# 1500015_ICLED_Featherwing_HW-V0-3.net
KiCad netlist of a schematic drawn in EAGLE
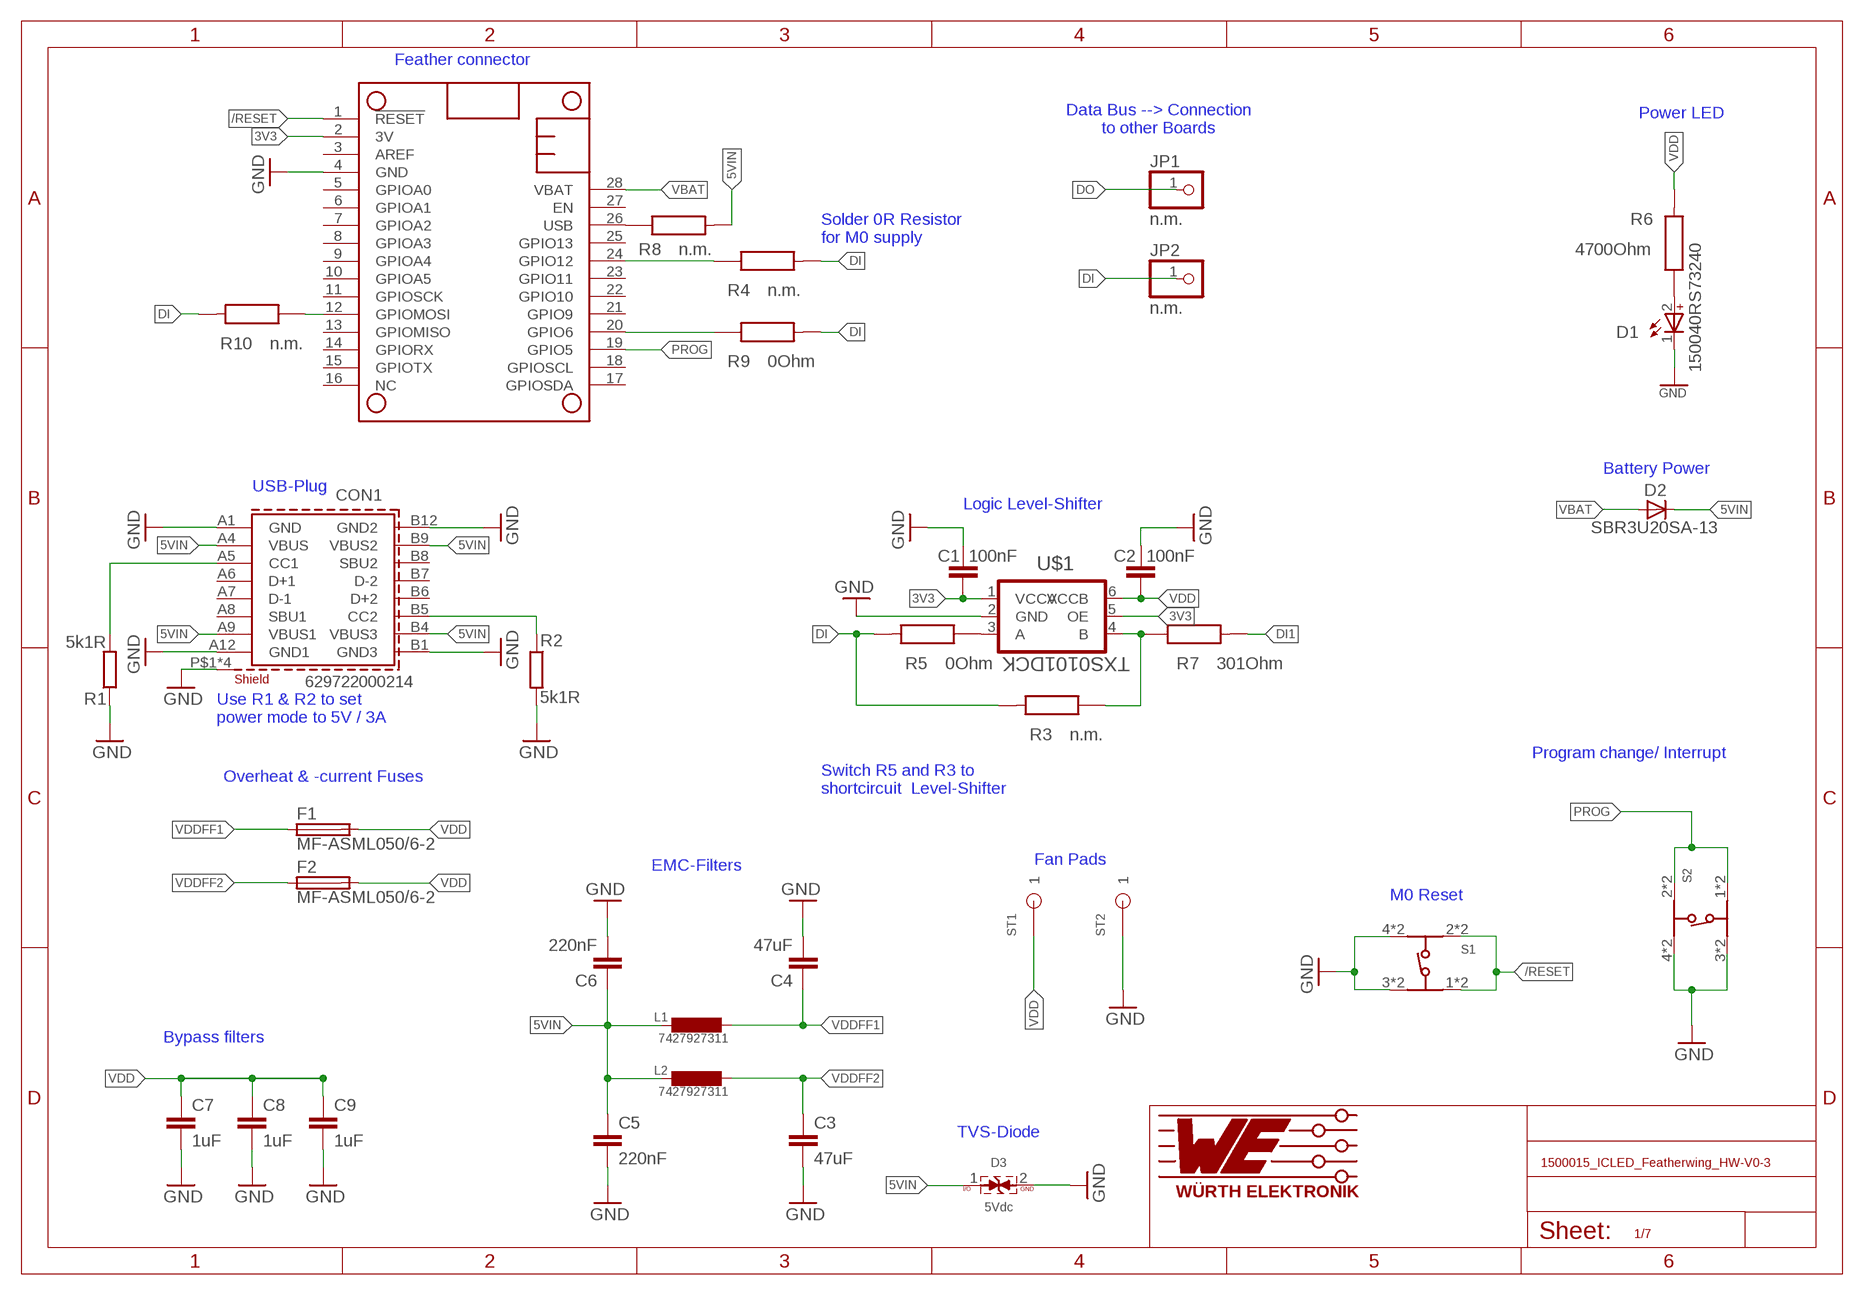
[diagram p0: schematic, sheet 1]
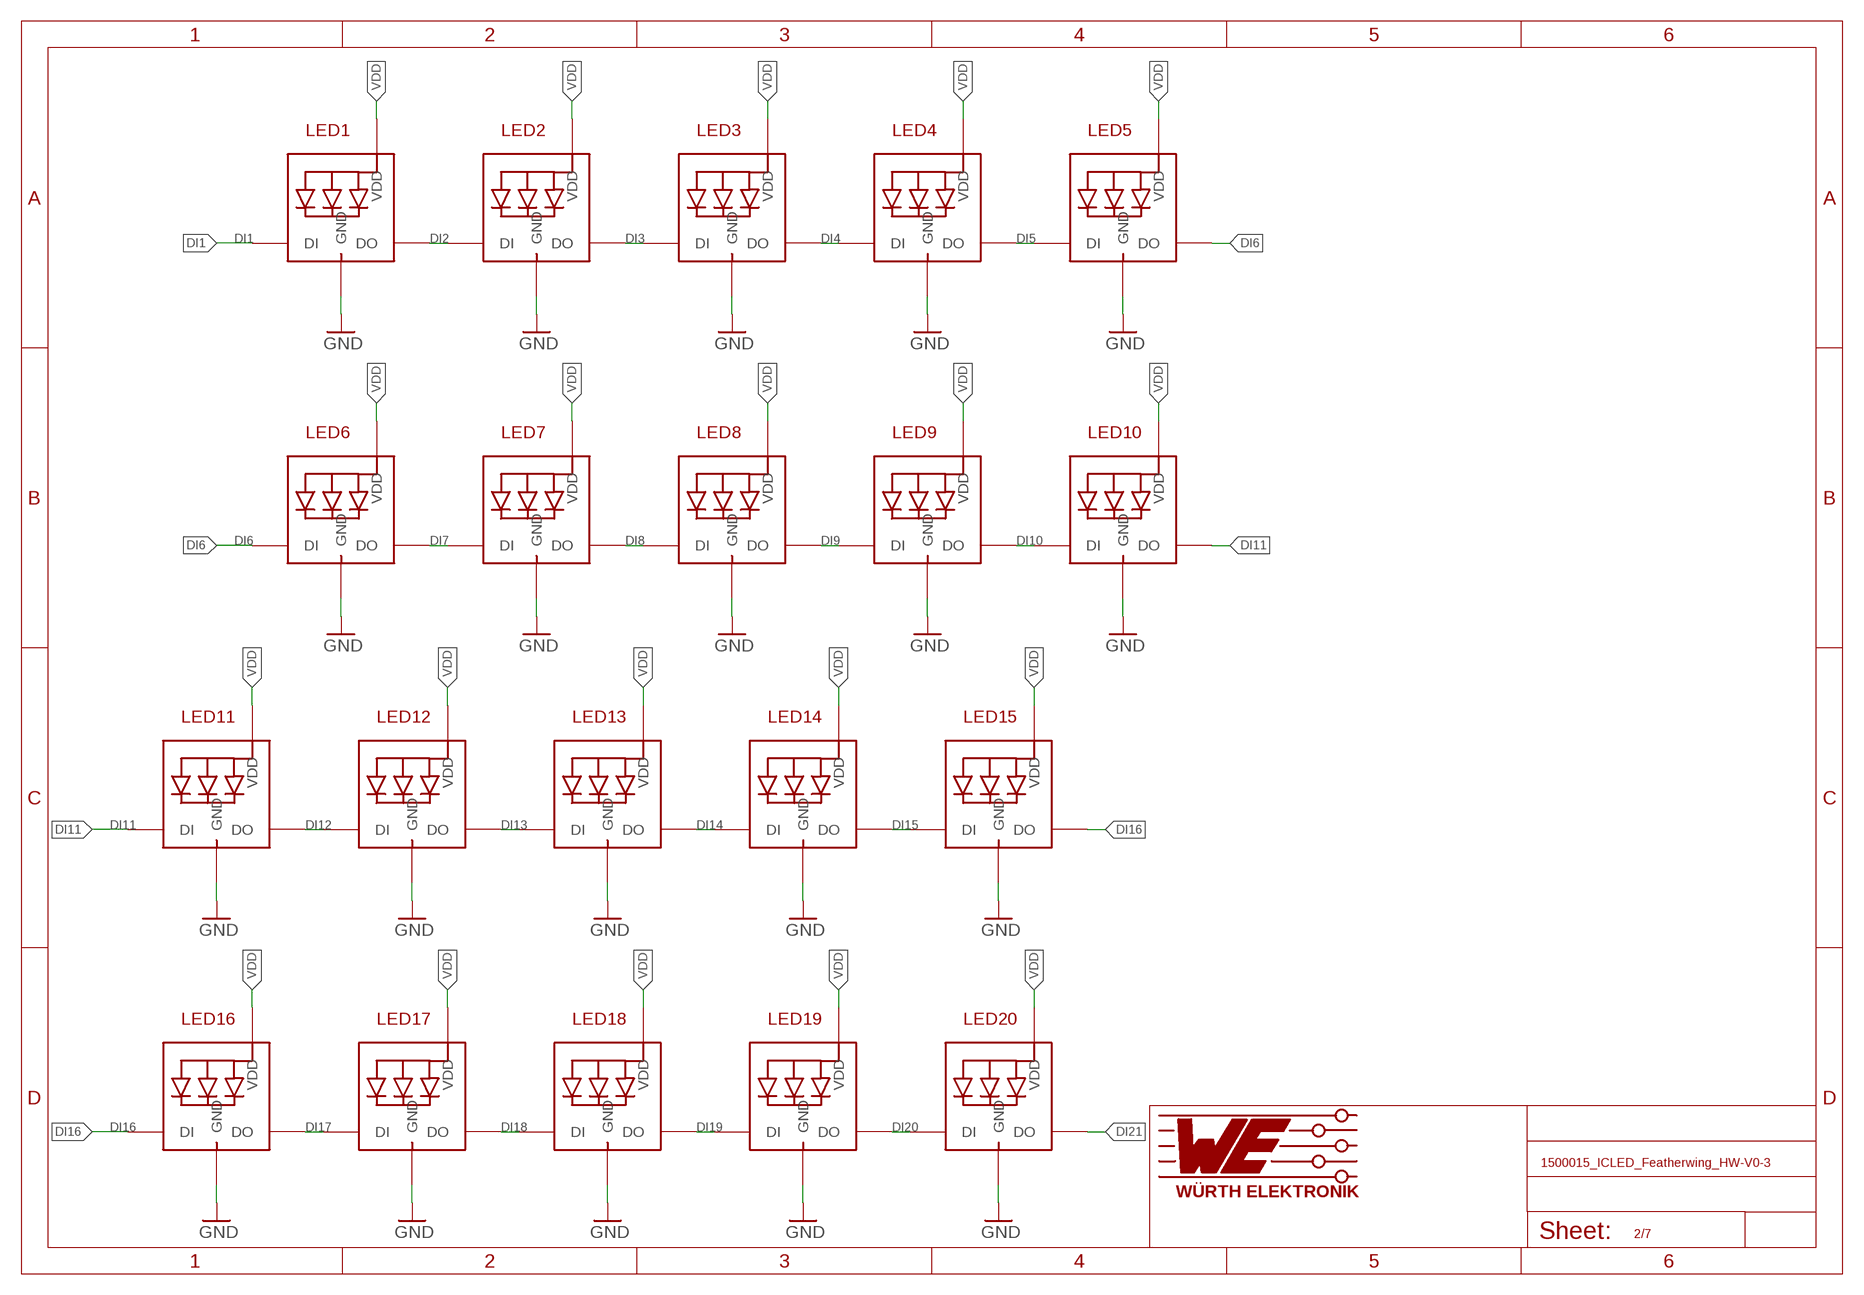
[diagram p1: schematic, sheet 2]
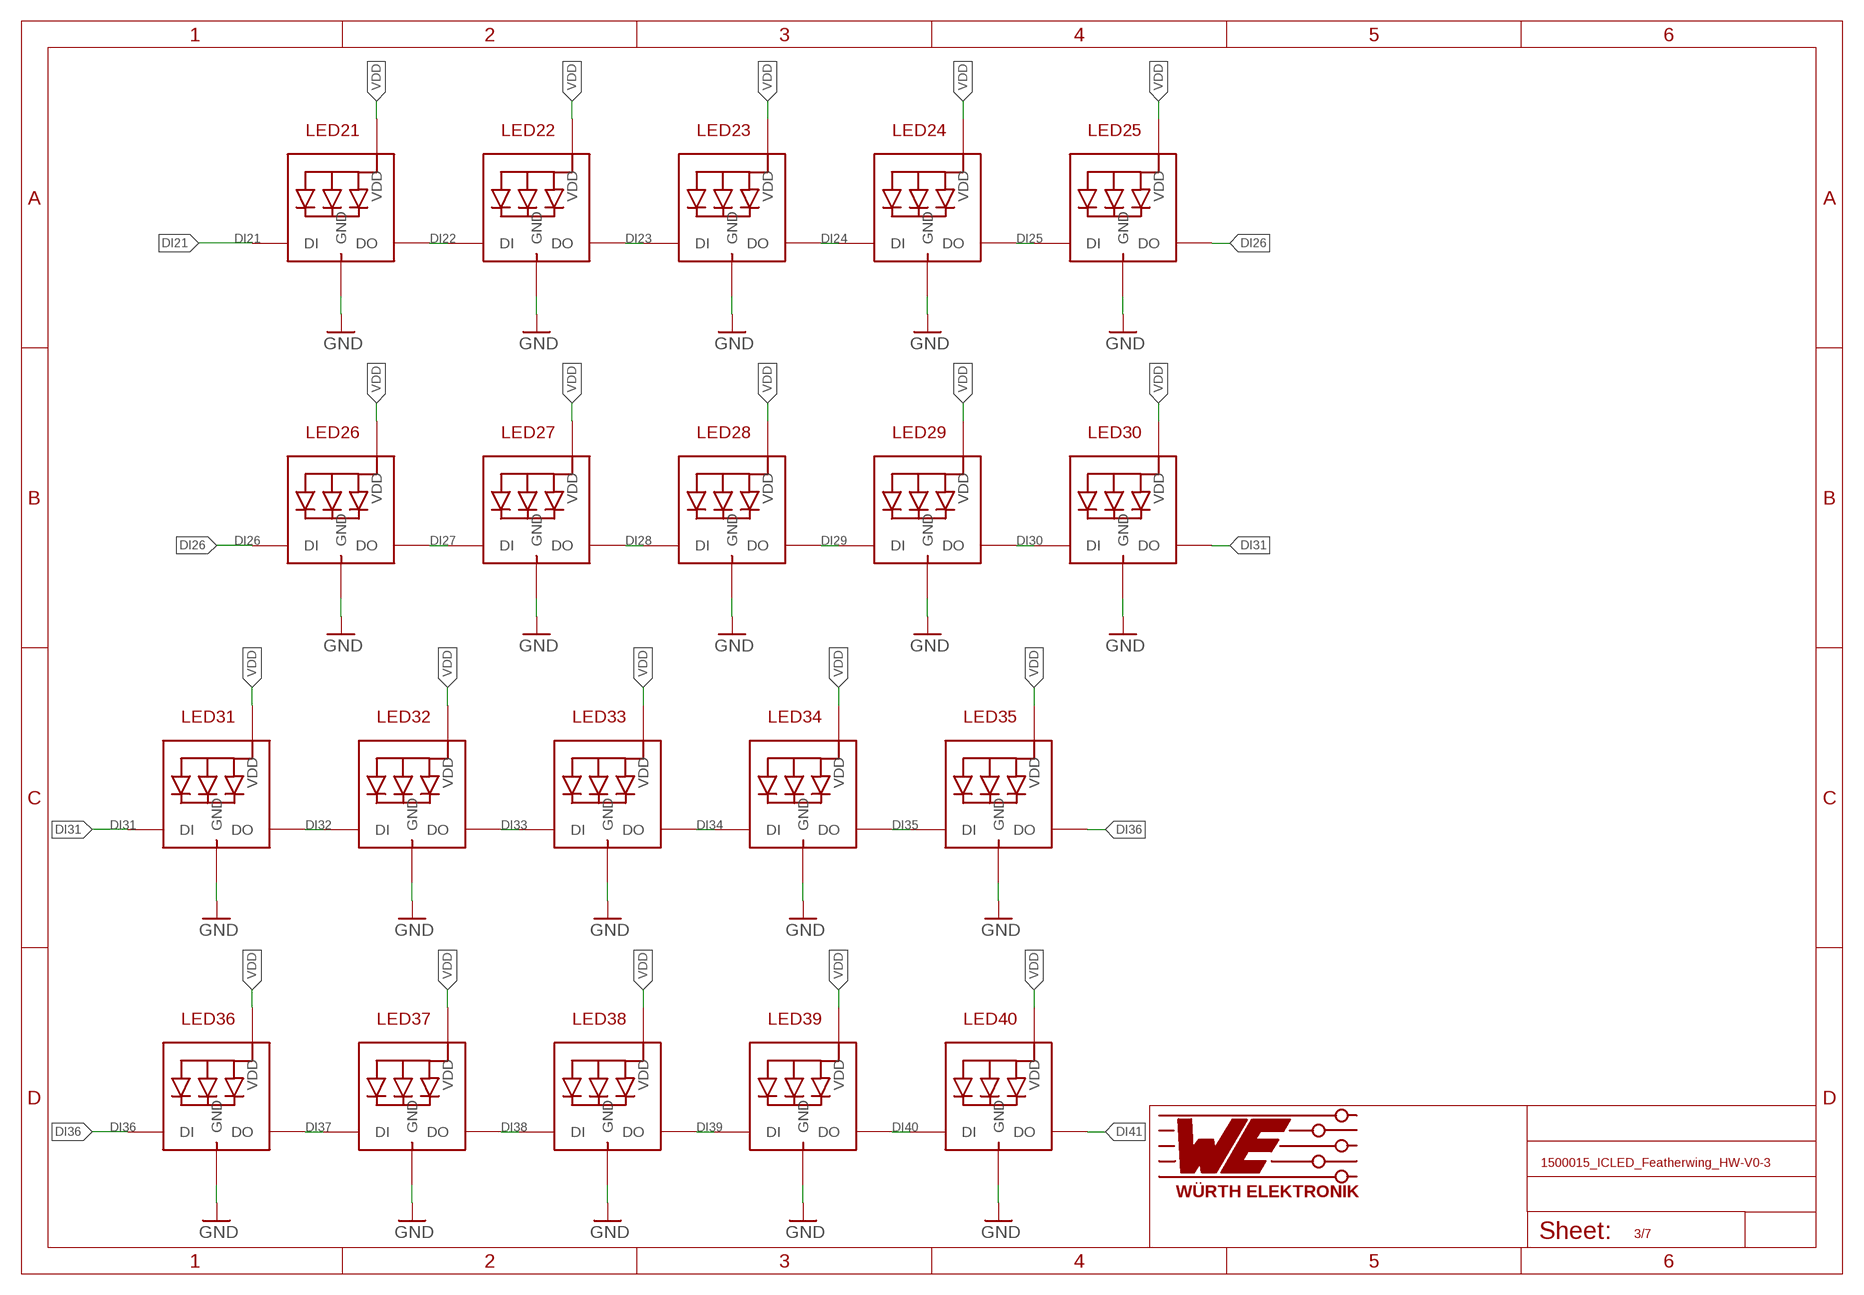
[diagram p2: schematic, sheet 3]
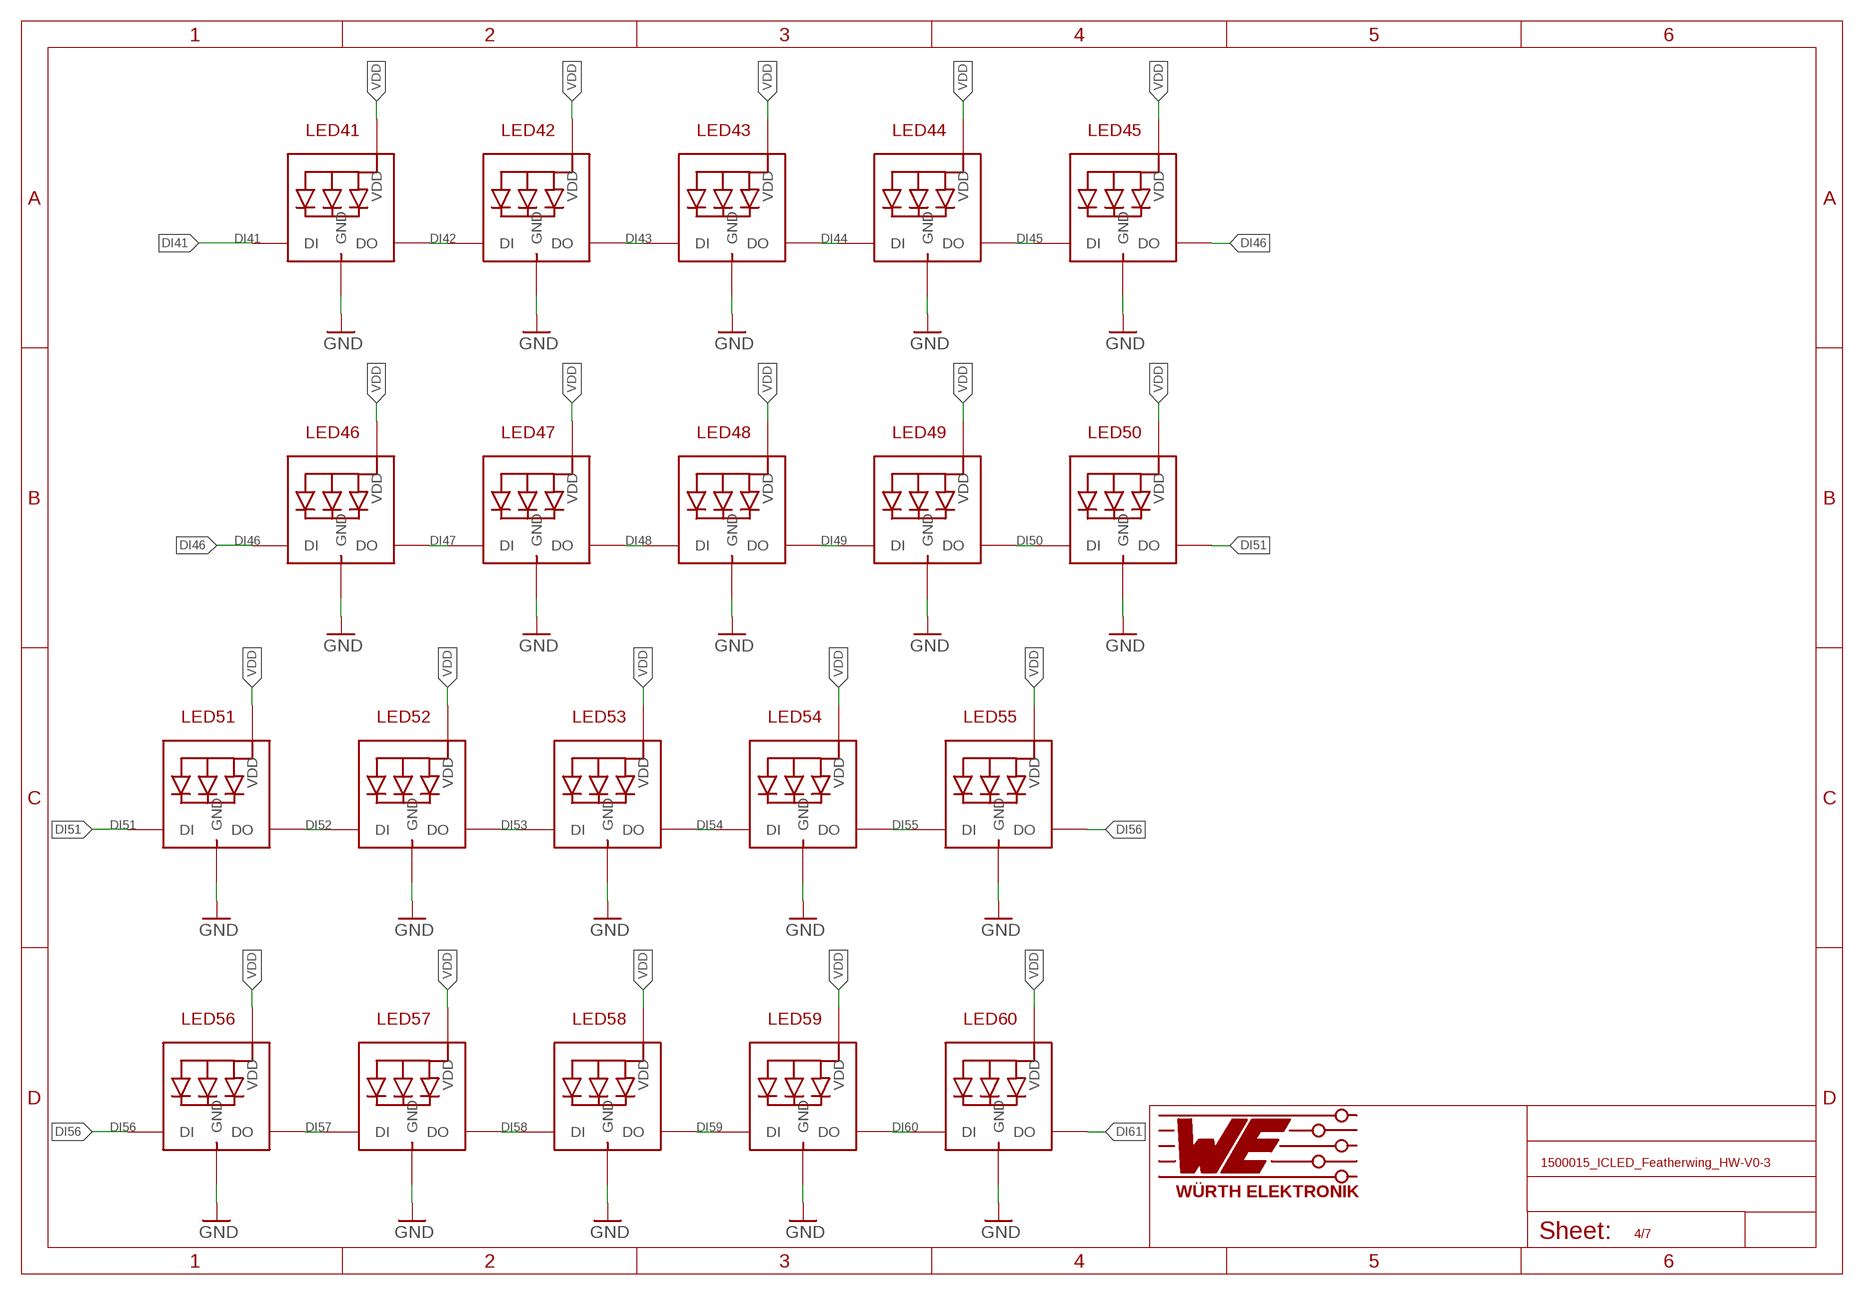
[diagram p3: schematic, sheet 4]
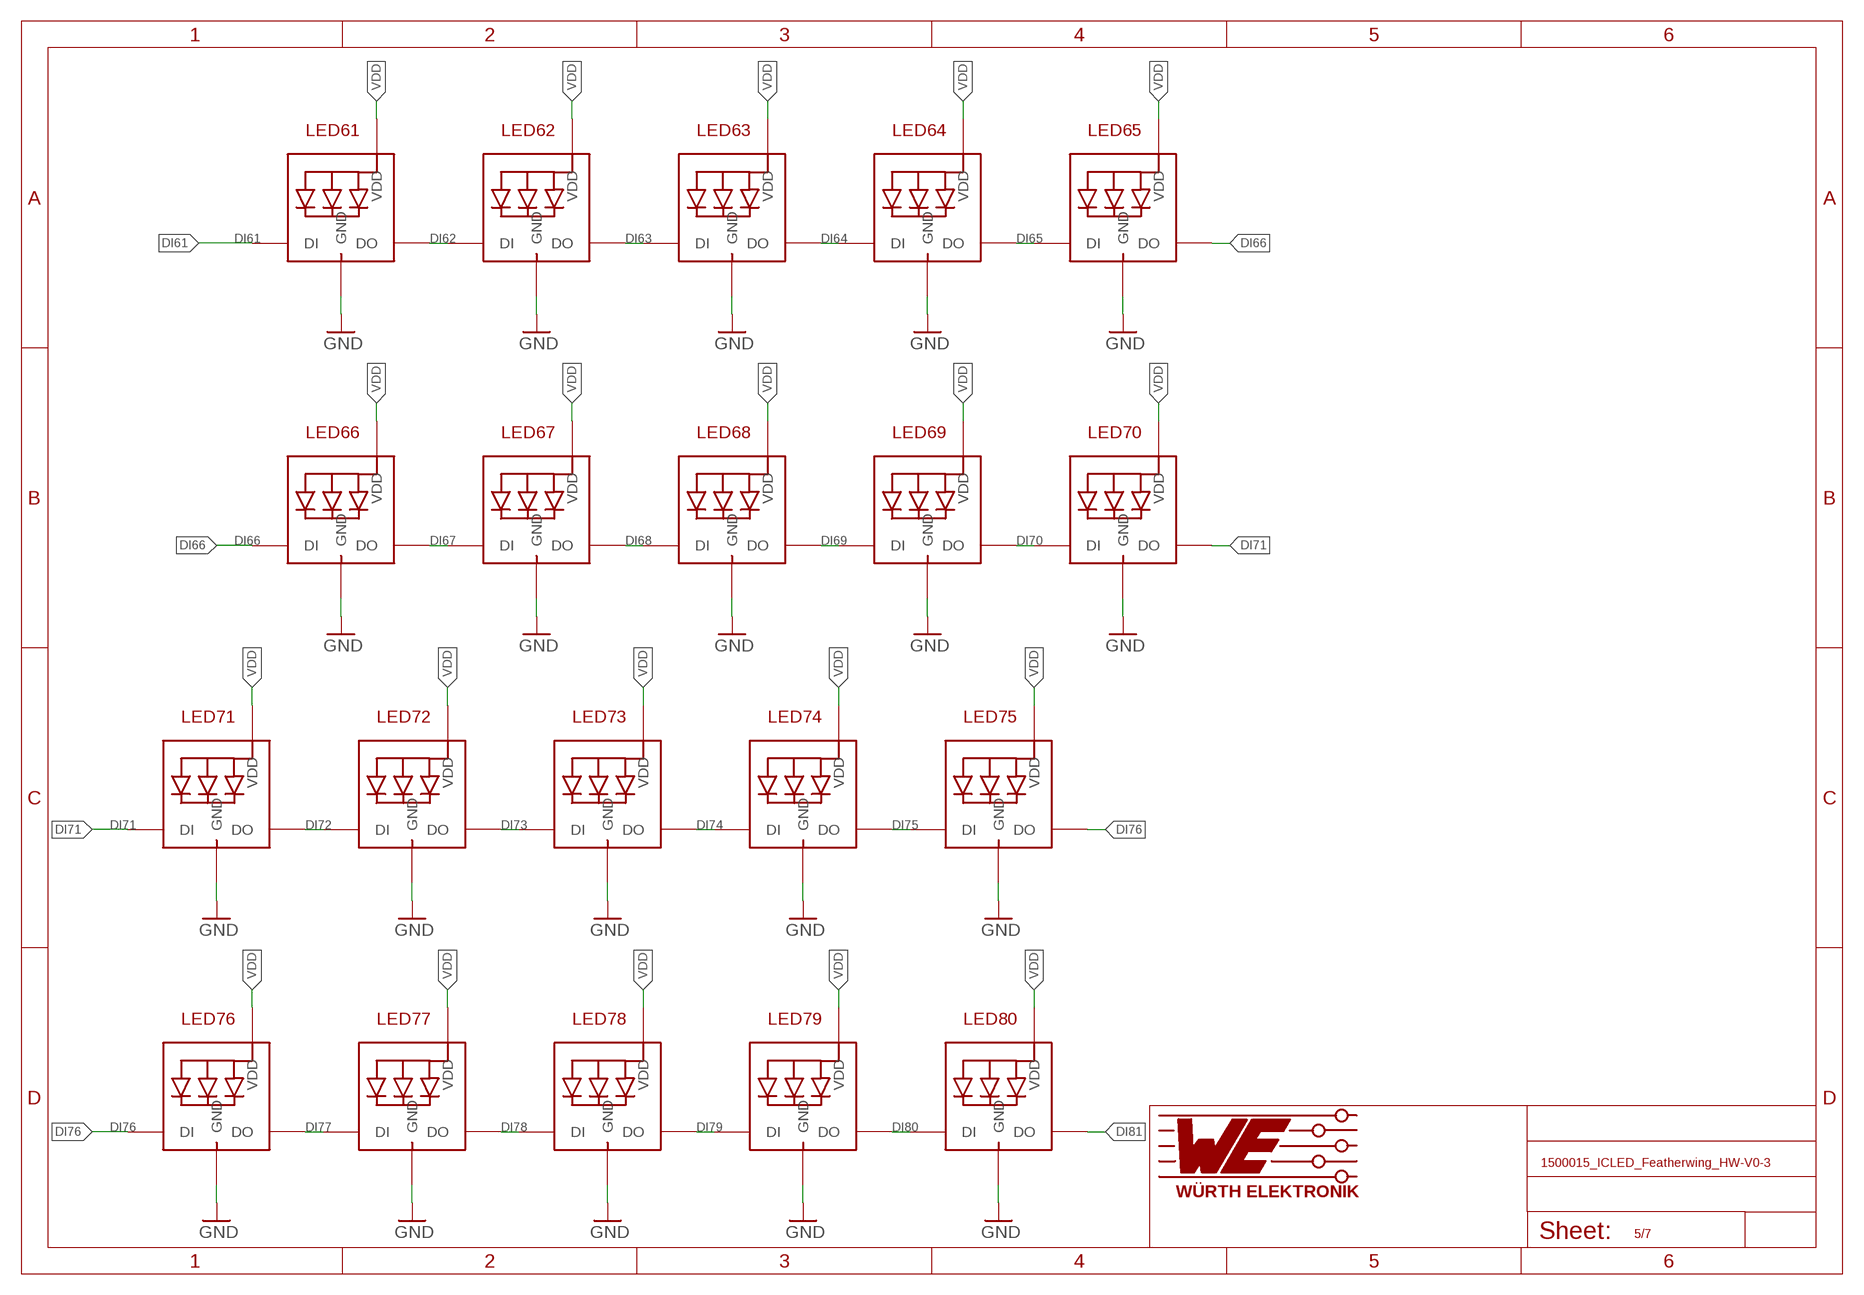
[diagram p4: schematic, sheet 5]
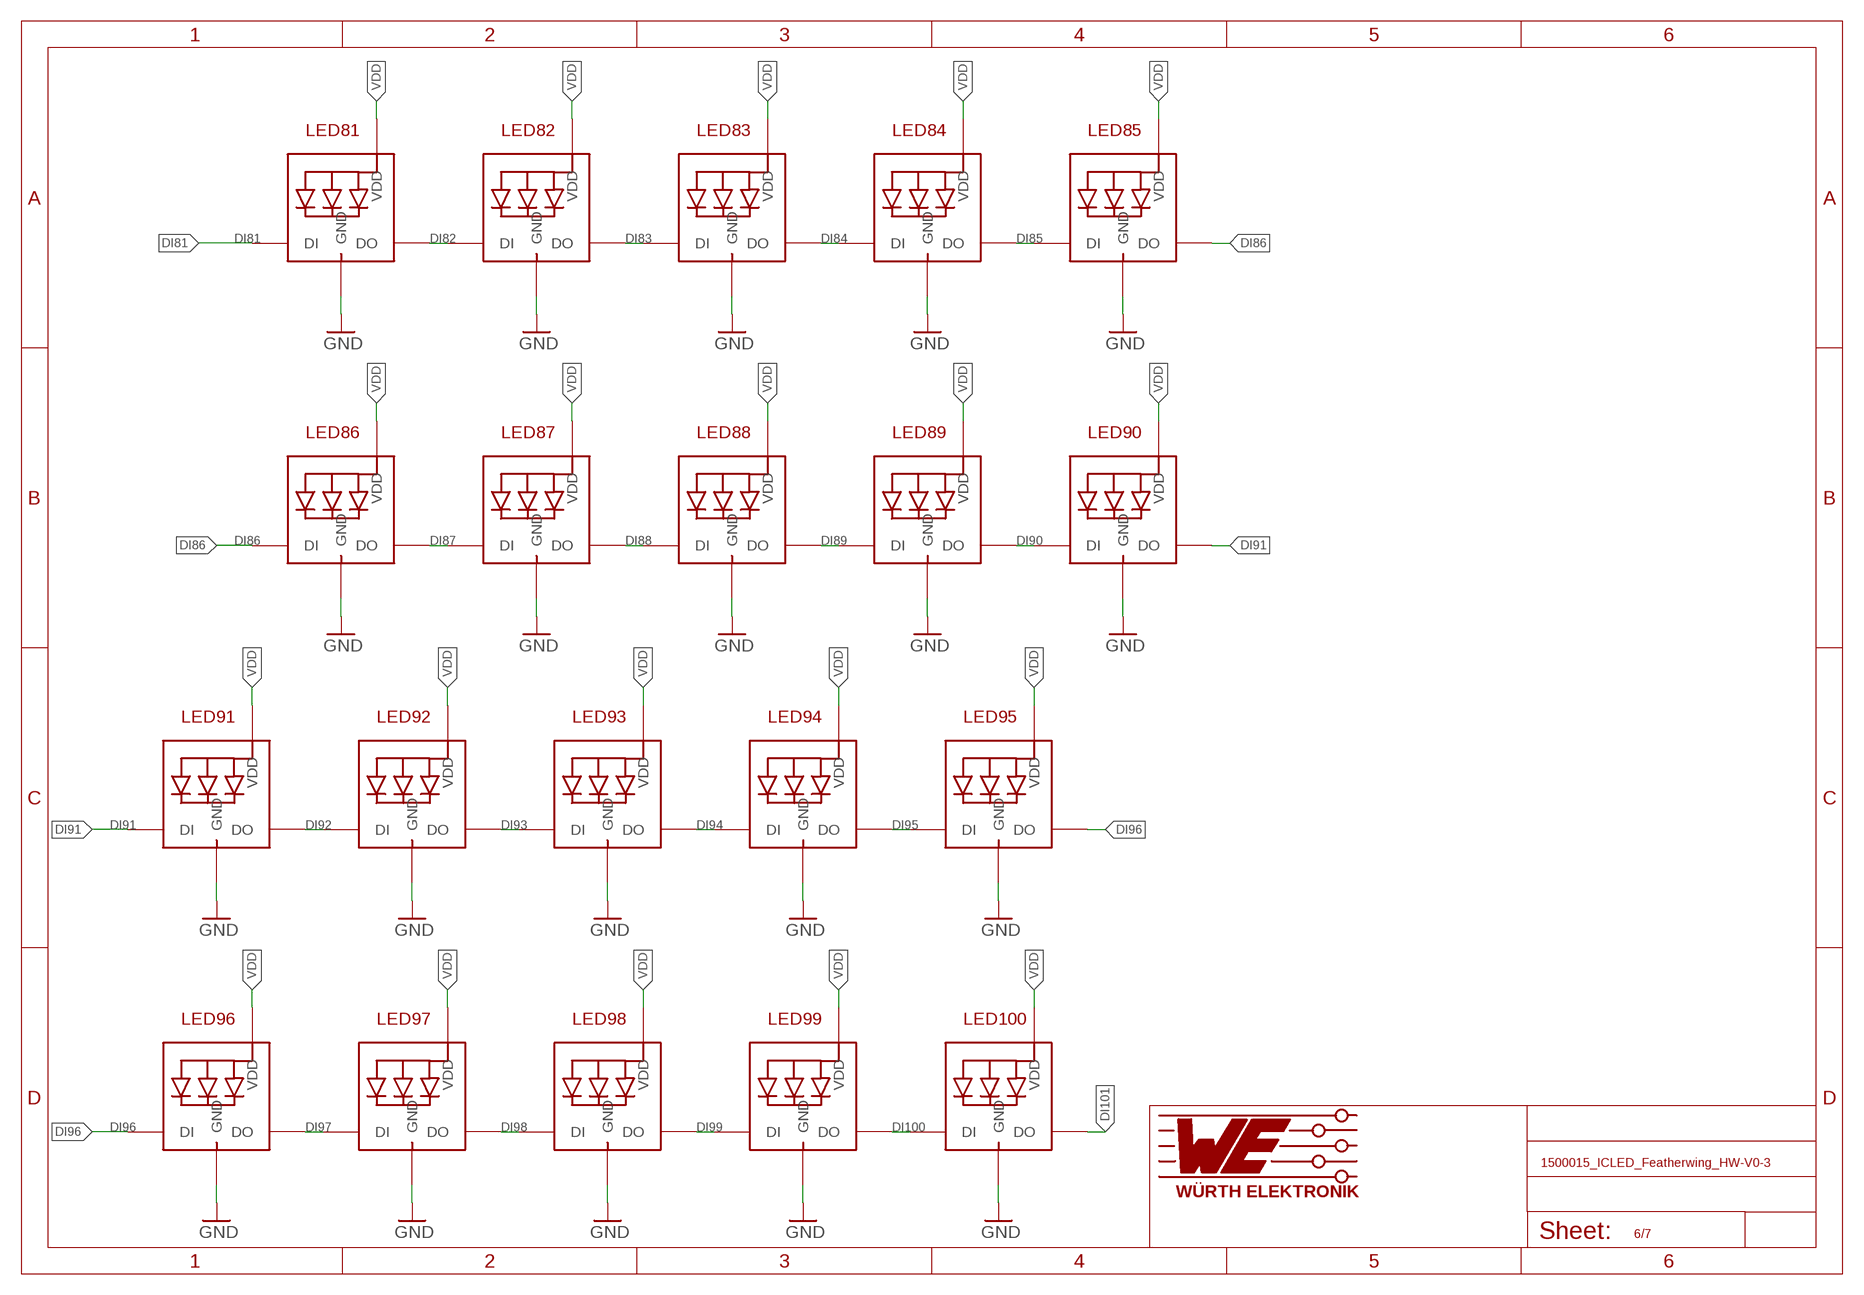
[diagram p5: schematic, sheet 6]
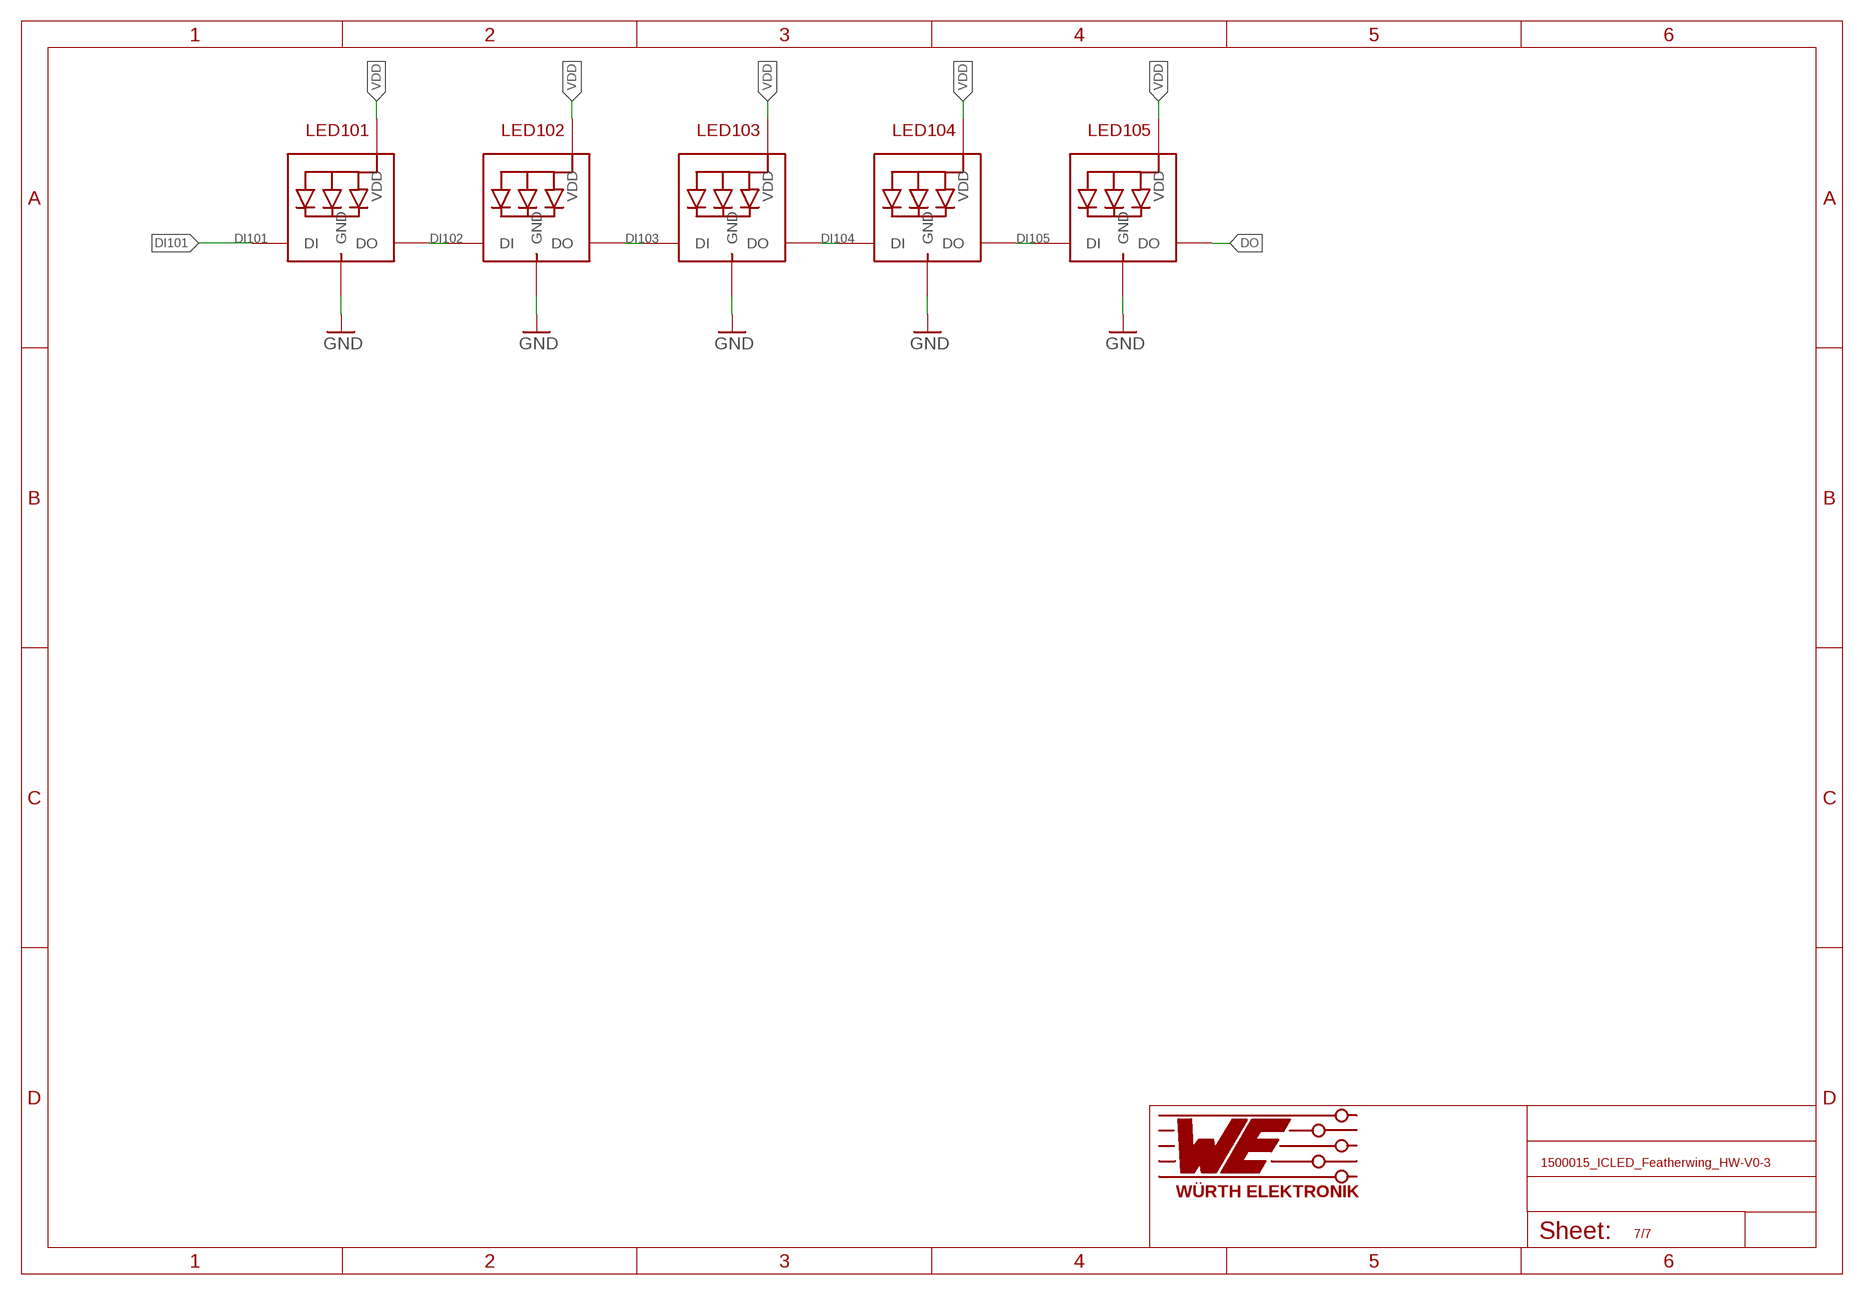
[diagram p6: schematic, sheet 7]

(export (version "E")
  (design (tool "Eeschema 10.0.6"))
  (components
    (comp (ref "LED41")
      (value "1312020030000")
      (footprint "eagle-import:1312020030000_FWANGEPASST")
      (fields (field (name "MANUFACTURER") "Würth Elektronik"))
      (libsource (lib "eagle-import") (part "1312020030000"))
    )
    (comp (ref "LED42")
      (value "1312020030000")
      (footprint "eagle-import:1312020030000_FWANGEPASST")
      (fields (field (name "MANUFACTURER") "Würth Elektronik"))
      (libsource (lib "eagle-import") (part "1312020030000"))
    )
    (comp (ref "LED43")
      (value "1312020030000")
      (footprint "eagle-import:1312020030000_FWANGEPASST")
      (fields (field (name "MANUFACTURER") "Würth Elektronik"))
      (libsource (lib "eagle-import") (part "1312020030000"))
    )
    (comp (ref "LED44")
      (value "1312020030000")
      (footprint "eagle-import:1312020030000_FWANGEPASST")
      (fields (field (name "MANUFACTURER") "Würth Elektronik"))
      (libsource (lib "eagle-import") (part "1312020030000"))
    )
    (comp (ref "LED45")
      (value "1312020030000")
      (footprint "eagle-import:1312020030000_FWANGEPASST")
      (fields (field (name "MANUFACTURER") "Würth Elektronik"))
      (libsource (lib "eagle-import") (part "1312020030000"))
    )
    (comp (ref "LED46")
      (value "1312020030000")
      (footprint "eagle-import:1312020030000_FWANGEPASST")
      (fields (field (name "MANUFACTURER") "Würth Elektronik"))
      (libsource (lib "eagle-import") (part "1312020030000"))
    )
    (comp (ref "LED47")
      (value "1312020030000")
      (footprint "eagle-import:1312020030000_FWANGEPASST")
      (fields (field (name "MANUFACTURER") "Würth Elektronik"))
      (libsource (lib "eagle-import") (part "1312020030000"))
    )
    (comp (ref "LED48")
      (value "1312020030000")
      (footprint "eagle-import:1312020030000_FWANGEPASST")
      (fields (field (name "MANUFACTURER") "Würth Elektronik"))
      (libsource (lib "eagle-import") (part "1312020030000"))
    )
    (comp (ref "LED49")
      (value "1312020030000")
      (footprint "eagle-import:1312020030000_FWANGEPASST")
      (fields (field (name "MANUFACTURER") "Würth Elektronik"))
      (libsource (lib "eagle-import") (part "1312020030000"))
    )
    (comp (ref "LED50")
      (value "1312020030000")
      (footprint "eagle-import:1312020030000_FWANGEPASST")
      (fields (field (name "MANUFACTURER") "Würth Elektronik"))
      (libsource (lib "eagle-import") (part "1312020030000"))
    )
    (comp (ref "LED51")
      (value "1312020030000")
      (footprint "eagle-import:1312020030000_FWANGEPASST")
      (fields (field (name "MANUFACTURER") "Würth Elektronik"))
      (libsource (lib "eagle-import") (part "1312020030000"))
    )
    (comp (ref "LED52")
      (value "1312020030000")
      (footprint "eagle-import:1312020030000_FWANGEPASST")
      (fields (field (name "MANUFACTURER") "Würth Elektronik"))
      (libsource (lib "eagle-import") (part "1312020030000"))
    )
    (comp (ref "LED53")
      (value "1312020030000")
      (footprint "eagle-import:1312020030000_FWANGEPASST")
      (fields (field (name "MANUFACTURER") "Würth Elektronik"))
      (libsource (lib "eagle-import") (part "1312020030000"))
    )
    (comp (ref "LED54")
      (value "1312020030000")
      (footprint "eagle-import:1312020030000_FWANGEPASST")
      (fields (field (name "MANUFACTURER") "Würth Elektronik"))
      (libsource (lib "eagle-import") (part "1312020030000"))
    )
    (comp (ref "LED55")
      (value "1312020030000")
      (footprint "eagle-import:1312020030000_FWANGEPASST")
      (fields (field (name "MANUFACTURER") "Würth Elektronik"))
      (libsource (lib "eagle-import") (part "1312020030000"))
    )
    (comp (ref "LED56")
      (value "1312020030000")
      (footprint "eagle-import:1312020030000_FWANGEPASST")
      (fields (field (name "MANUFACTURER") "Würth Elektronik"))
      (libsource (lib "eagle-import") (part "1312020030000"))
    )
    (comp (ref "LED57")
      (value "1312020030000")
      (footprint "eagle-import:1312020030000_FWANGEPASST")
      (fields (field (name "MANUFACTURER") "Würth Elektronik"))
      (libsource (lib "eagle-import") (part "1312020030000"))
    )
    (comp (ref "LED58")
      (value "1312020030000")
      (footprint "eagle-import:1312020030000_FWANGEPASST")
      (fields (field (name "MANUFACTURER") "Würth Elektronik"))
      (libsource (lib "eagle-import") (part "1312020030000"))
    )
    (comp (ref "LED59")
      (value "1312020030000")
      (footprint "eagle-import:1312020030000_FWANGEPASST")
      (fields (field (name "MANUFACTURER") "Würth Elektronik"))
      (libsource (lib "eagle-import") (part "1312020030000"))
    )
    (comp (ref "LED60")
      (value "1312020030000")
      (footprint "eagle-import:1312020030000_FWANGEPASST")
      (fields (field (name "MANUFACTURER") "Würth Elektronik"))
      (libsource (lib "eagle-import") (part "1312020030000"))
    )
    (comp (ref "LED61")
      (value "1312020030000")
      (footprint "eagle-import:1312020030000_FWANGEPASST")
      (fields (field (name "MANUFACTURER") "Würth Elektronik"))
      (libsource (lib "eagle-import") (part "1312020030000"))
    )
    (comp (ref "LED62")
      (value "1312020030000")
      (footprint "eagle-import:1312020030000_FWANGEPASST")
      (fields (field (name "MANUFACTURER") "Würth Elektronik"))
      (libsource (lib "eagle-import") (part "1312020030000"))
    )
    (comp (ref "LED63")
      (value "1312020030000")
      (footprint "eagle-import:1312020030000_FWANGEPASST")
      (fields (field (name "MANUFACTURER") "Würth Elektronik"))
      (libsource (lib "eagle-import") (part "1312020030000"))
    )
    (comp (ref "LED64")
      (value "1312020030000")
      (footprint "eagle-import:1312020030000_FWANGEPASST")
      (fields (field (name "MANUFACTURER") "Würth Elektronik"))
      (libsource (lib "eagle-import") (part "1312020030000"))
    )
    (comp (ref "LED65")
      (value "1312020030000")
      (footprint "eagle-import:1312020030000_FWANGEPASST")
      (fields (field (name "MANUFACTURER") "Würth Elektronik"))
      (libsource (lib "eagle-import") (part "1312020030000"))
    )
    (comp (ref "LED66")
      (value "1312020030000")
      (footprint "eagle-import:1312020030000_FWANGEPASST")
      (fields (field (name "MANUFACTURER") "Würth Elektronik"))
      (libsource (lib "eagle-import") (part "1312020030000"))
    )
    (comp (ref "LED67")
      (value "1312020030000")
      (footprint "eagle-import:1312020030000_FWANGEPASST")
      (fields (field (name "MANUFACTURER") "Würth Elektronik"))
      (libsource (lib "eagle-import") (part "1312020030000"))
    )
    (comp (ref "LED68")
      (value "1312020030000")
      (footprint "eagle-import:1312020030000_FWANGEPASST")
      (fields (field (name "MANUFACTURER") "Würth Elektronik"))
      (libsource (lib "eagle-import") (part "1312020030000"))
    )
    (comp (ref "LED69")
      (value "1312020030000")
      (footprint "eagle-import:1312020030000_FWANGEPASST")
      (fields (field (name "MANUFACTURER") "Würth Elektronik"))
      (libsource (lib "eagle-import") (part "1312020030000"))
    )
    (comp (ref "LED70")
      (value "1312020030000")
      (footprint "eagle-import:1312020030000_FWANGEPASST")
      (fields (field (name "MANUFACTURER") "Würth Elektronik"))
      (libsource (lib "eagle-import") (part "1312020030000"))
    )
    (comp (ref "LED71")
      (value "1312020030000")
      (footprint "eagle-import:1312020030000_FWANGEPASST")
      (fields (field (name "MANUFACTURER") "Würth Elektronik"))
      (libsource (lib "eagle-import") (part "1312020030000"))
    )
    (comp (ref "LED72")
      (value "1312020030000")
      (footprint "eagle-import:1312020030000_FWANGEPASST")
      (fields (field (name "MANUFACTURER") "Würth Elektronik"))
      (libsource (lib "eagle-import") (part "1312020030000"))
    )
    (comp (ref "LED73")
      (value "1312020030000")
      (footprint "eagle-import:1312020030000_FWANGEPASST")
      (fields (field (name "MANUFACTURER") "Würth Elektronik"))
      (libsource (lib "eagle-import") (part "1312020030000"))
    )
    (comp (ref "LED74")
      (value "1312020030000")
      (footprint "eagle-import:1312020030000_FWANGEPASST")
      (fields (field (name "MANUFACTURER") "Würth Elektronik"))
      (libsource (lib "eagle-import") (part "1312020030000"))
    )
    (comp (ref "LED75")
      (value "1312020030000")
      (footprint "eagle-import:1312020030000_FWANGEPASST")
      (fields (field (name "MANUFACTURER") "Würth Elektronik"))
      (libsource (lib "eagle-import") (part "1312020030000"))
    )
    (comp (ref "LED76")
      (value "1312020030000")
      (footprint "eagle-import:1312020030000_FWANGEPASST")
      (fields (field (name "MANUFACTURER") "Würth Elektronik"))
      (libsource (lib "eagle-import") (part "1312020030000"))
    )
    (comp (ref "LED77")
      (value "1312020030000")
      (footprint "eagle-import:1312020030000_FWANGEPASST")
      (fields (field (name "MANUFACTURER") "Würth Elektronik"))
      (libsource (lib "eagle-import") (part "1312020030000"))
    )
    (comp (ref "LED78")
      (value "1312020030000")
      (footprint "eagle-import:1312020030000_FWANGEPASST")
      (fields (field (name "MANUFACTURER") "Würth Elektronik"))
      (libsource (lib "eagle-import") (part "1312020030000"))
    )
    (comp (ref "LED79")
      (value "1312020030000")
      (footprint "eagle-import:1312020030000_FWANGEPASST")
      (fields (field (name "MANUFACTURER") "Würth Elektronik"))
      (libsource (lib "eagle-import") (part "1312020030000"))
    )
    (comp (ref "LED80")
      (value "1312020030000")
      (footprint "eagle-import:1312020030000_FWANGEPASST")
      (fields (field (name "MANUFACTURER") "Würth Elektronik"))
      (libsource (lib "eagle-import") (part "1312020030000"))
    )
    (comp (ref "LED1")
      (value "1312020030000")
      (footprint "eagle-import:1312020030000_FWANGEPASST")
      (fields (field (name "MANUFACTURER") "Würth Elektronik"))
      (libsource (lib "eagle-import") (part "1312020030000"))
    )
    (comp (ref "LED2")
      (value "1312020030000")
      (footprint "eagle-import:1312020030000_FWANGEPASST")
      (fields (field (name "MANUFACTURER") "Würth Elektronik"))
      (libsource (lib "eagle-import") (part "1312020030000"))
    )
    (comp (ref "LED3")
      (value "1312020030000")
      (footprint "eagle-import:1312020030000_FWANGEPASST")
      (fields (field (name "MANUFACTURER") "Würth Elektronik"))
      (libsource (lib "eagle-import") (part "1312020030000"))
    )
    (comp (ref "LED4")
      (value "1312020030000")
      (footprint "eagle-import:1312020030000_FWANGEPASST")
      (fields (field (name "MANUFACTURER") "Würth Elektronik"))
      (libsource (lib "eagle-import") (part "1312020030000"))
    )
    (comp (ref "LED5")
      (value "1312020030000")
      (footprint "eagle-import:1312020030000_FWANGEPASST")
      (fields (field (name "MANUFACTURER") "Würth Elektronik"))
      (libsource (lib "eagle-import") (part "1312020030000"))
    )
    (comp (ref "LED6")
      (value "1312020030000")
      (footprint "eagle-import:1312020030000_FWANGEPASST")
      (fields (field (name "MANUFACTURER") "Würth Elektronik"))
      (libsource (lib "eagle-import") (part "1312020030000"))
    )
    (comp (ref "LED7")
      (value "1312020030000")
      (footprint "eagle-import:1312020030000_FWANGEPASST")
      (fields (field (name "MANUFACTURER") "Würth Elektronik"))
      (libsource (lib "eagle-import") (part "1312020030000"))
    )
    (comp (ref "LED8")
      (value "1312020030000")
      (footprint "eagle-import:1312020030000_FWANGEPASST")
      (fields (field (name "MANUFACTURER") "Würth Elektronik"))
      (libsource (lib "eagle-import") (part "1312020030000"))
    )
    (comp (ref "LED9")
      (value "1312020030000")
      (footprint "eagle-import:1312020030000_FWANGEPASST")
      (fields (field (name "MANUFACTURER") "Würth Elektronik"))
      (libsource (lib "eagle-import") (part "1312020030000"))
    )
    (comp (ref "LED10")
      (value "1312020030000")
      (footprint "eagle-import:1312020030000_FWANGEPASST")
      (fields (field (name "MANUFACTURER") "Würth Elektronik"))
      (libsource (lib "eagle-import") (part "1312020030000"))
    )
    (comp (ref "LED11")
      (value "1312020030000")
      (footprint "eagle-import:1312020030000_FWANGEPASST")
      (fields (field (name "MANUFACTURER") "Würth Elektronik"))
      (libsource (lib "eagle-import") (part "1312020030000"))
    )
    (comp (ref "LED12")
      (value "1312020030000")
      (footprint "eagle-import:1312020030000_FWANGEPASST")
      (fields (field (name "MANUFACTURER") "Würth Elektronik"))
      (libsource (lib "eagle-import") (part "1312020030000"))
    )
    (comp (ref "LED13")
      (value "1312020030000")
      (footprint "eagle-import:1312020030000_FWANGEPASST")
      (fields (field (name "MANUFACTURER") "Würth Elektronik"))
      (libsource (lib "eagle-import") (part "1312020030000"))
    )
    (comp (ref "LED14")
      (value "1312020030000")
      (footprint "eagle-import:1312020030000_FWANGEPASST")
      (fields (field (name "MANUFACTURER") "Würth Elektronik"))
      (libsource (lib "eagle-import") (part "1312020030000"))
    )
    (comp (ref "LED15")
      (value "1312020030000")
      (footprint "eagle-import:1312020030000_FWANGEPASST")
      (fields (field (name "MANUFACTURER") "Würth Elektronik"))
      (libsource (lib "eagle-import") (part "1312020030000"))
    )
    (comp (ref "LED16")
      (value "1312020030000")
      (footprint "eagle-import:1312020030000_FWANGEPASST")
      (fields (field (name "MANUFACTURER") "Würth Elektronik"))
      (libsource (lib "eagle-import") (part "1312020030000"))
    )
    (comp (ref "LED17")
      (value "1312020030000")
      (footprint "eagle-import:1312020030000_FWANGEPASST")
      (fields (field (name "MANUFACTURER") "Würth Elektronik"))
      (libsource (lib "eagle-import") (part "1312020030000"))
    )
    (comp (ref "LED18")
      (value "1312020030000")
      (footprint "eagle-import:1312020030000_FWANGEPASST")
      (fields (field (name "MANUFACTURER") "Würth Elektronik"))
      (libsource (lib "eagle-import") (part "1312020030000"))
    )
    (comp (ref "LED19")
      (value "1312020030000")
      (footprint "eagle-import:1312020030000_FWANGEPASST")
      (fields (field (name "MANUFACTURER") "Würth Elektronik"))
      (libsource (lib "eagle-import") (part "1312020030000"))
    )
    (comp (ref "LED20")
      (value "1312020030000")
      (footprint "eagle-import:1312020030000_FWANGEPASST")
      (fields (field (name "MANUFACTURER") "Würth Elektronik"))
      (libsource (lib "eagle-import") (part "1312020030000"))
    )
    (comp (ref "C1")
      (value "100nF")
      (footprint "eagle-import:C0402_IPC")
      (fields (field (name "MANUFACTURER") "Würth Elektronik"))
      (libsource (lib "eagle-import") (part "C0402_IPC100NF"))
    )
    (comp (ref "C2")
      (value "100nF")
      (footprint "eagle-import:C0402_IPC")
      (fields (field (name "MANUFACTURER") "Würth Elektronik"))
      (libsource (lib "eagle-import") (part "C0402_IPC100NF"))
    )
    (comp (ref "C3")
      (value "47uF")
      (footprint "eagle-import:C0805")
      (fields
        (field (name "MANUFACTURER") "Würth Elektronik")
        (field (name "NR") "885012107006")
        (field (name "SPG") "6.3V")
      )
      (libsource (lib "eagle-import") (part "C0805"))
    )
    (comp (ref "C4")
      (value "47uF")
      (footprint "eagle-import:C0805")
      (fields
        (field (name "MANUFACTURER") "Würth Elektronik")
        (field (name "NR") "885012107006")
        (field (name "SPG") "6.3V")
      )
      (libsource (lib "eagle-import") (part "C0805"))
    )
    (comp (ref "C5")
      (value "220nF")
      (footprint "eagle-import:C0603_IPC")
      (fields
        (field (name "MANUFACTURER") "Wurth Elektronik")
        (field (name "NR") "885012206125")
        (field (name "SPG") "50V")
        (field (name "TOL") "5%")
      )
      (libsource (lib "eagle-import") (part "C0603_IPC220N"))
    )
    (comp (ref "C6")
      (value "220nF")
      (footprint "eagle-import:C0603_IPC")
      (fields
        (field (name "MANUFACTURER") "Wurth Elektronik")
        (field (name "NR") "885012206125")
        (field (name "SPG") "50V")
        (field (name "TOL") "5%")
      )
      (libsource (lib "eagle-import") (part "C0603_IPC220N"))
    )
    (comp (ref "C7")
      (value "1uF")
      (footprint "eagle-import:C0402_IPC")
      (fields (field (name "MANUFACTURER") "Würth Elektronik"))
      (libsource (lib "eagle-import") (part "C0402_IPC1UF"))
    )
    (comp (ref "C8")
      (value "1uF")
      (footprint "eagle-import:C0402_IPC")
      (fields (field (name "MANUFACTURER") "Würth Elektronik"))
      (libsource (lib "eagle-import") (part "C0402_IPC1UF"))
    )
    (comp (ref "C9")
      (value "1uF")
      (footprint "eagle-import:C0402_IPC")
      (fields (field (name "MANUFACTURER") "Würth Elektronik"))
      (libsource (lib "eagle-import") (part "C0402_IPC1UF"))
    )
    (comp (ref "CON1")
      (value "629722000214")
      (footprint "eagle-import:629722000214")
      (libsource (lib "eagle-import") (part "629722000214"))
    )
    (comp (ref "D1")
      (value "150040RS73240")
      (footprint "eagle-import:WL-SMCC_0402")
      (libsource (lib "eagle-import") (part "WL-SMCC_0402_150040RS73240"))
    )
    (comp (ref "D2")
      (value "SBR3U20SA-13")
      (footprint "eagle-import:SBR3U20SA")
      (fields (field (name "MANUFACTURER") "Diodes Inc"))
      (libsource (lib "eagle-import") (part "SBR3U20SA-13"))
    )
    (comp (ref "D3")
      (value "5Vdc")
      (footprint "eagle-import:WE-TVS_DFN1610-2L")
      (libsource (lib "eagle-import") (part "WE-TVS_DFN1610-2L_824032815"))
    )
    (comp (ref "F1")
      (value "MF-ASML050/6-2")
      (footprint "eagle-import:0402")
      (fields (field (name "MANUFACTURER") "Bourns"))
      (libsource (lib "eagle-import") (part "ERB-RD2R00X"))
    )
    (comp (ref "F2")
      (value "MF-ASML050/6-2")
      (footprint "eagle-import:0402")
      (fields (field (name "MANUFACTURER") "Bourns"))
      (libsource (lib "eagle-import") (part "ERB-RD2R00X"))
    )
    (comp (ref "JP1")
      (value "n.m.")
      (footprint "eagle-import:1X01_R")
      (libsource (lib "eagle-import") (part "PINHD-1X1/R"))
    )
    (comp (ref "JP2")
      (value "n.m.")
      (footprint "eagle-import:1X01_R")
      (libsource (lib "eagle-import") (part "PINHD-1X1/R"))
    )
    (comp (ref "L1")
      (value "7427927311")
      (footprint "eagle-import:L0402_WE_FERRIT")
      (fields (field (name "MANUFACTURER") "Würth Elektronik "))
      (libsource (lib "eagle-import") (part "LL0402_WE_FERRIT"))
    )
    (comp (ref "L2")
      (value "7427927311")
      (footprint "eagle-import:L0402_WE_FERRIT")
      (fields (field (name "MANUFACTURER") "Würth Elektronik "))
      (libsource (lib "eagle-import") (part "LL0402_WE_FERRIT"))
    )
    (comp (ref "MS1")
      (value "FEATHERWING")
      (footprint "eagle-import:FEATHERWING")
      (libsource (lib "eagle-import") (part "FEATHERWING"))
    )
    (comp (ref "R1")
      (value "5k1R")
      (footprint "eagle-import:R0402_IPC")
      (fields (field (name "NR") " RC0402FR-075K1L"))
      (libsource (lib "eagle-import") (part "R0402_IPC10KR"))
    )
    (comp (ref "R2")
      (value "5k1R")
      (footprint "eagle-import:R0402_IPC")
      (fields (field (name "NR") " RC0402FR-075K1L"))
      (libsource (lib "eagle-import") (part "R0402_IPC10KR"))
    )
    (comp (ref "R3")
      (value "n.m.")
      (footprint "eagle-import:WRIS-RSKS_0603_WAVE")
      (libsource (lib "eagle-import") (part "WRIS-RSKS_0603_WAVE_560112116001"))
    )
    (comp (ref "R4")
      (value "n.m.")
      (footprint "eagle-import:WRIS-RSKS_0402")
      (libsource (lib "eagle-import") (part "WRIS-RSKS_0402_560112110001"))
    )
    (comp (ref "R5")
      (value "0Ohm")
      (footprint "eagle-import:WRIS-RSKS_0603_WAVE")
      (libsource (lib "eagle-import") (part "WRIS-RSKS_0603_WAVE_560112116001"))
    )
    (comp (ref "R6")
      (value "4700Ohm")
      (footprint "eagle-import:WRIS-RSKS_0402")
      (libsource (lib "eagle-import") (part "WRIS-RSKS_0402_560112110245"))
    )
    (comp (ref "R7")
      (value "301Ohm")
      (footprint "eagle-import:WRIS-RSKS_0402")
      (libsource (lib "eagle-import") (part "WRIS-RSKS_0402_560112110092"))
    )
    (comp (ref "R8")
      (value "n.m.")
      (footprint "eagle-import:WRIS-RSKS_0402")
      (libsource (lib "eagle-import") (part "WRIS-RSKS_0402_560112110001"))
    )
    (comp (ref "R9")
      (value "0Ohm")
      (footprint "eagle-import:WRIS-RSKS_0603_WAVE")
      (libsource (lib "eagle-import") (part "WRIS-RSKS_0603_WAVE_560112116001"))
    )
    (comp (ref "R10")
      (value "n.m.")
      (footprint "eagle-import:WRIS-RSKS_0603_WAVE")
      (libsource (lib "eagle-import") (part "WRIS-RSKS_0603_WAVE_560112116001"))
    )
    (comp (ref "S1")
      (value "434331013822")
      (footprint "eagle-import:434331013822_ICLEDFW_ANGEPASST")
      (fields (field (name "MANUFACTURER") "Würth Elektronik"))
      (libsource (lib "eagle-import") (part "434331013822_ANGEPASST"))
    )
    (comp (ref "S2")
      (value "434331013822")
      (footprint "eagle-import:434331013822_ICLEDFW_ANGEPASST")
      (fields (field (name "MANUFACTURER") "Würth Elektronik"))
      (libsource (lib "eagle-import") (part "434331013822_ANGEPASST"))
    )
    (comp (ref "ST1")
      (value "1_5X1MM")
      (footprint "eagle-import:1_5X1MM")
      (libsource (lib "eagle-import") (part "1_5X1MM"))
    )
    (comp (ref "ST2")
      (value "1_5X1MM")
      (footprint "eagle-import:1_5X1MM")
      (libsource (lib "eagle-import") (part "1_5X1MM"))
    )
    (comp (ref "U$1")
      (value "TXS0101DCK")
      (footprint "eagle-import:SC70")
      (fields (field (name "MANUFACTURER") "Texas Instruments"))
      (libsource (lib "eagle-import") (part "TXS0101DCK"))
    )
    (comp (ref "LED81")
      (value "1312020030000")
      (footprint "eagle-import:1312020030000_FWANGEPASST")
      (fields (field (name "MANUFACTURER") "Würth Elektronik"))
      (libsource (lib "eagle-import") (part "1312020030000"))
    )
    (comp (ref "LED82")
      (value "1312020030000")
      (footprint "eagle-import:1312020030000_FWANGEPASST")
      (fields (field (name "MANUFACTURER") "Würth Elektronik"))
      (libsource (lib "eagle-import") (part "1312020030000"))
    )
    (comp (ref "LED83")
      (value "1312020030000")
      (footprint "eagle-import:1312020030000_FWANGEPASST")
      (fields (field (name "MANUFACTURER") "Würth Elektronik"))
      (libsource (lib "eagle-import") (part "1312020030000"))
    )
    (comp (ref "LED84")
      (value "1312020030000")
      (footprint "eagle-import:1312020030000_FWANGEPASST")
      (fields (field (name "MANUFACTURER") "Würth Elektronik"))
      (libsource (lib "eagle-import") (part "1312020030000"))
    )
    (comp (ref "LED85")
      (value "1312020030000")
      (footprint "eagle-import:1312020030000_FWANGEPASST")
      (fields (field (name "MANUFACTURER") "Würth Elektronik"))
      (libsource (lib "eagle-import") (part "1312020030000"))
    )
    (comp (ref "LED86")
      (value "1312020030000")
      (footprint "eagle-import:1312020030000_FWANGEPASST")
      (fields (field (name "MANUFACTURER") "Würth Elektronik"))
      (libsource (lib "eagle-import") (part "1312020030000"))
    )
    (comp (ref "LED87")
      (value "1312020030000")
      (footprint "eagle-import:1312020030000_FWANGEPASST")
      (fields (field (name "MANUFACTURER") "Würth Elektronik"))
      (libsource (lib "eagle-import") (part "1312020030000"))
    )
    (comp (ref "LED88")
      (value "1312020030000")
      (footprint "eagle-import:1312020030000_FWANGEPASST")
      (fields (field (name "MANUFACTURER") "Würth Elektronik"))
      (libsource (lib "eagle-import") (part "1312020030000"))
    )
    (comp (ref "LED89")
      (value "1312020030000")
      (footprint "eagle-import:1312020030000_FWANGEPASST")
      (fields (field (name "MANUFACTURER") "Würth Elektronik"))
      (libsource (lib "eagle-import") (part "1312020030000"))
    )
    (comp (ref "LED90")
      (value "1312020030000")
      (footprint "eagle-import:1312020030000_FWANGEPASST")
      (fields (field (name "MANUFACTURER") "Würth Elektronik"))
      (libsource (lib "eagle-import") (part "1312020030000"))
    )
    (comp (ref "LED91")
      (value "1312020030000")
      (footprint "eagle-import:1312020030000_FWANGEPASST")
      (fields (field (name "MANUFACTURER") "Würth Elektronik"))
      (libsource (lib "eagle-import") (part "1312020030000"))
    )
    (comp (ref "LED92")
      (value "1312020030000")
      (footprint "eagle-import:1312020030000_FWANGEPASST")
      (fields (field (name "MANUFACTURER") "Würth Elektronik"))
      (libsource (lib "eagle-import") (part "1312020030000"))
    )
    (comp (ref "LED93")
      (value "1312020030000")
      (footprint "eagle-import:1312020030000_FWANGEPASST")
      (fields (field (name "MANUFACTURER") "Würth Elektronik"))
      (libsource (lib "eagle-import") (part "1312020030000"))
    )
    (comp (ref "LED94")
      (value "1312020030000")
      (footprint "eagle-import:1312020030000_FWANGEPASST")
      (fields (field (name "MANUFACTURER") "Würth Elektronik"))
      (libsource (lib "eagle-import") (part "1312020030000"))
    )
    (comp (ref "LED95")
      (value "1312020030000")
      (footprint "eagle-import:1312020030000_FWANGEPASST")
      (fields (field (name "MANUFACTURER") "Würth Elektronik"))
      (libsource (lib "eagle-import") (part "1312020030000"))
    )
    (comp (ref "LED96")
      (value "1312020030000")
      (footprint "eagle-import:1312020030000_FWANGEPASST")
      (fields (field (name "MANUFACTURER") "Würth Elektronik"))
      (libsource (lib "eagle-import") (part "1312020030000"))
    )
    (comp (ref "LED97")
      (value "1312020030000")
      (footprint "eagle-import:1312020030000_FWANGEPASST")
      (fields (field (name "MANUFACTURER") "Würth Elektronik"))
      (libsource (lib "eagle-import") (part "1312020030000"))
    )
    (comp (ref "LED98")
      (value "1312020030000")
      (footprint "eagle-import:1312020030000_FWANGEPASST")
      (fields (field (name "MANUFACTURER") "Würth Elektronik"))
      (libsource (lib "eagle-import") (part "1312020030000"))
    )
    (comp (ref "LED99")
      (value "1312020030000")
      (footprint "eagle-import:1312020030000_FWANGEPASST")
      (fields (field (name "MANUFACTURER") "Würth Elektronik"))
      (libsource (lib "eagle-import") (part "1312020030000"))
    )
    (comp (ref "LED100")
      (value "1312020030000")
      (footprint "eagle-import:1312020030000_FWANGEPASST")
      (fields (field (name "MANUFACTURER") "Würth Elektronik"))
      (libsource (lib "eagle-import") (part "1312020030000"))
    )
    (comp (ref "LED101")
      (value "1312020030000")
      (footprint "eagle-import:1312020030000_FWANGEPASST")
      (fields (field (name "MANUFACTURER") "Würth Elektronik"))
      (libsource (lib "eagle-import") (part "1312020030000"))
    )
    (comp (ref "LED102")
      (value "1312020030000")
      (footprint "eagle-import:1312020030000_FWANGEPASST")
      (fields (field (name "MANUFACTURER") "Würth Elektronik"))
      (libsource (lib "eagle-import") (part "1312020030000"))
    )
    (comp (ref "LED103")
      (value "1312020030000")
      (footprint "eagle-import:1312020030000_FWANGEPASST")
      (fields (field (name "MANUFACTURER") "Würth Elektronik"))
      (libsource (lib "eagle-import") (part "1312020030000"))
    )
    (comp (ref "LED104")
      (value "1312020030000")
      (footprint "eagle-import:1312020030000_FWANGEPASST")
      (fields (field (name "MANUFACTURER") "Würth Elektronik"))
      (libsource (lib "eagle-import") (part "1312020030000"))
    )
    (comp (ref "LED105")
      (value "1312020030000")
      (footprint "eagle-import:1312020030000_FWANGEPASST")
      (fields (field (name "MANUFACTURER") "Würth Elektronik"))
      (libsource (lib "eagle-import") (part "1312020030000"))
    )
    (comp (ref "LED21")
      (value "1312020030000")
      (footprint "eagle-import:1312020030000_FWANGEPASST")
      (fields (field (name "MANUFACTURER") "Würth Elektronik"))
      (libsource (lib "eagle-import") (part "1312020030000"))
    )
    (comp (ref "LED22")
      (value "1312020030000")
      (footprint "eagle-import:1312020030000_FWANGEPASST")
      (fields (field (name "MANUFACTURER") "Würth Elektronik"))
      (libsource (lib "eagle-import") (part "1312020030000"))
    )
    (comp (ref "LED23")
      (value "1312020030000")
      (footprint "eagle-import:1312020030000_FWANGEPASST")
      (fields (field (name "MANUFACTURER") "Würth Elektronik"))
      (libsource (lib "eagle-import") (part "1312020030000"))
    )
    (comp (ref "LED24")
      (value "1312020030000")
      (footprint "eagle-import:1312020030000_FWANGEPASST")
      (fields (field (name "MANUFACTURER") "Würth Elektronik"))
      (libsource (lib "eagle-import") (part "1312020030000"))
    )
    (comp (ref "LED25")
      (value "1312020030000")
      (footprint "eagle-import:1312020030000_FWANGEPASST")
      (fields (field (name "MANUFACTURER") "Würth Elektronik"))
      (libsource (lib "eagle-import") (part "1312020030000"))
    )
    (comp (ref "LED26")
      (value "1312020030000")
      (footprint "eagle-import:1312020030000_FWANGEPASST")
      (fields (field (name "MANUFACTURER") "Würth Elektronik"))
      (libsource (lib "eagle-import") (part "1312020030000"))
    )
    (comp (ref "LED27")
      (value "1312020030000")
      (footprint "eagle-import:1312020030000_FWANGEPASST")
      (fields (field (name "MANUFACTURER") "Würth Elektronik"))
      (libsource (lib "eagle-import") (part "1312020030000"))
    )
    (comp (ref "LED28")
      (value "1312020030000")
      (footprint "eagle-import:1312020030000_FWANGEPASST")
      (fields (field (name "MANUFACTURER") "Würth Elektronik"))
      (libsource (lib "eagle-import") (part "1312020030000"))
    )
    (comp (ref "LED29")
      (value "1312020030000")
      (footprint "eagle-import:1312020030000_FWANGEPASST")
      (fields (field (name "MANUFACTURER") "Würth Elektronik"))
      (libsource (lib "eagle-import") (part "1312020030000"))
    )
    (comp (ref "LED30")
      (value "1312020030000")
      (footprint "eagle-import:1312020030000_FWANGEPASST")
      (fields (field (name "MANUFACTURER") "Würth Elektronik"))
      (libsource (lib "eagle-import") (part "1312020030000"))
    )
    (comp (ref "LED31")
      (value "1312020030000")
      (footprint "eagle-import:1312020030000_FWANGEPASST")
      (fields (field (name "MANUFACTURER") "Würth Elektronik"))
      (libsource (lib "eagle-import") (part "1312020030000"))
    )
    (comp (ref "LED32")
      (value "1312020030000")
      (footprint "eagle-import:1312020030000_FWANGEPASST")
      (fields (field (name "MANUFACTURER") "Würth Elektronik"))
      (libsource (lib "eagle-import") (part "1312020030000"))
    )
    (comp (ref "LED33")
      (value "1312020030000")
      (footprint "eagle-import:1312020030000_FWANGEPASST")
      (fields (field (name "MANUFACTURER") "Würth Elektronik"))
      (libsource (lib "eagle-import") (part "1312020030000"))
    )
    (comp (ref "LED34")
      (value "1312020030000")
      (footprint "eagle-import:1312020030000_FWANGEPASST")
      (fields (field (name "MANUFACTURER") "Würth Elektronik"))
      (libsource (lib "eagle-import") (part "1312020030000"))
    )
    (comp (ref "LED35")
      (value "1312020030000")
      (footprint "eagle-import:1312020030000_FWANGEPASST")
      (fields (field (name "MANUFACTURER") "Würth Elektronik"))
      (libsource (lib "eagle-import") (part "1312020030000"))
    )
    (comp (ref "LED36")
      (value "1312020030000")
      (footprint "eagle-import:1312020030000_FWANGEPASST")
      (fields (field (name "MANUFACTURER") "Würth Elektronik"))
      (libsource (lib "eagle-import") (part "1312020030000"))
    )
    (comp (ref "LED37")
      (value "1312020030000")
      (footprint "eagle-import:1312020030000_FWANGEPASST")
      (fields (field (name "MANUFACTURER") "Würth Elektronik"))
      (libsource (lib "eagle-import") (part "1312020030000"))
    )
    (comp (ref "LED38")
      (value "1312020030000")
      (footprint "eagle-import:1312020030000_FWANGEPASST")
      (fields (field (name "MANUFACTURER") "Würth Elektronik"))
      (libsource (lib "eagle-import") (part "1312020030000"))
    )
    (comp (ref "LED39")
      (value "1312020030000")
      (footprint "eagle-import:1312020030000_FWANGEPASST")
      (fields (field (name "MANUFACTURER") "Würth Elektronik"))
      (libsource (lib "eagle-import") (part "1312020030000"))
    )
    (comp (ref "LED40")
      (value "1312020030000")
      (footprint "eagle-import:1312020030000_FWANGEPASST")
      (fields (field (name "MANUFACTURER") "Würth Elektronik"))
      (libsource (lib "eagle-import") (part "1312020030000"))
    )
  )
  (nets
    (net (code "1") (name "3V3") (class "Default")
      (node (ref "C1") (pin "2") (pinfunction "2_2") (pintype "passive"))
      (node (ref "MS1") (pin "2") (pinfunction "3V_2") (pintype "power_in"))
      (node (ref "U$1") (pin "1") (pinfunction "VCCA_1") (pintype "input"))
      (node (ref "U$1") (pin "5") (pinfunction "OE_5") (pintype "input"))
    )
    (net (code "2") (name "5VIN") (class "Default")
      (node (ref "C5") (pin "1") (pinfunction "1_1") (pintype "passive"))
      (node (ref "C6") (pin "1") (pinfunction "1_1") (pintype "passive"))
      (node (ref "CON1") (pin "A4") (pinfunction "VBUS_A4") (pintype "passive"))
      (node (ref "CON1") (pin "A9") (pinfunction "VBUS1_A9") (pintype "passive"))
      (node (ref "CON1") (pin "B4") (pinfunction "VBUS3_B4") (pintype "passive"))
      (node (ref "CON1") (pin "B9") (pinfunction "VBUS2_B9") (pintype "passive"))
      (node (ref "D2") (pin "K") (pinfunction "C_K") (pintype "passive"))
      (node (ref "D3") (pin "1") (pinfunction "I/O_1") (pintype "passive"))
      (node (ref "L1") (pin "P$2") (pinfunction "2_P$2") (pintype "passive"))
      (node (ref "L2") (pin "P$2") (pinfunction "2_P$2") (pintype "passive"))
      (node (ref "R8") (pin "2") (pinfunction "2_2") (pintype "passive"))
    )
    (net (code "3") (name "DI") (class "Default")
      (node (ref "JP2") (pin "1") (pinfunction "1_1") (pintype "passive"))
      (node (ref "R10") (pin "2") (pinfunction "2_2") (pintype "passive"))
      (node (ref "R3") (pin "2") (pinfunction "2_2") (pintype "passive"))
      (node (ref "R4") (pin "2") (pinfunction "2_2") (pintype "passive"))
      (node (ref "R5") (pin "2") (pinfunction "2_2") (pintype "passive"))
      (node (ref "R9") (pin "2") (pinfunction "2_2") (pintype "passive"))
    )
    (net (code "4") (name "DI1") (class "Default")
      (node (ref "LED1") (pin "3-DIN") (pinfunction "DI_3-DIN") (pintype "input"))
      (node (ref "R7") (pin "2") (pinfunction "2_2") (pintype "passive"))
    )
    (net (code "5") (name "DI2") (class "Default")
      (node (ref "LED1") (pin "1-DOUT") (pinfunction "DO_1-DOUT") (pintype "output"))
      (node (ref "LED2") (pin "3-DIN") (pinfunction "DI_3-DIN") (pintype "input"))
    )
    (net (code "6") (name "DI3") (class "Default")
      (node (ref "LED2") (pin "1-DOUT") (pinfunction "DO_1-DOUT") (pintype "output"))
      (node (ref "LED3") (pin "3-DIN") (pinfunction "DI_3-DIN") (pintype "input"))
    )
    (net (code "7") (name "DI4") (class "Default")
      (node (ref "LED3") (pin "1-DOUT") (pinfunction "DO_1-DOUT") (pintype "output"))
      (node (ref "LED4") (pin "3-DIN") (pinfunction "DI_3-DIN") (pintype "input"))
    )
    (net (code "8") (name "DI5") (class "Default")
      (node (ref "LED4") (pin "1-DOUT") (pinfunction "DO_1-DOUT") (pintype "output"))
      (node (ref "LED5") (pin "3-DIN") (pinfunction "DI_3-DIN") (pintype "input"))
    )
    (net (code "9") (name "DI6") (class "Default")
      (node (ref "LED5") (pin "1-DOUT") (pinfunction "DO_1-DOUT") (pintype "output"))
      (node (ref "LED6") (pin "3-DIN") (pinfunction "DI_3-DIN") (pintype "input"))
    )
    (net (code "10") (name "DI7") (class "Default")
      (node (ref "LED6") (pin "1-DOUT") (pinfunction "DO_1-DOUT") (pintype "output"))
      (node (ref "LED7") (pin "3-DIN") (pinfunction "DI_3-DIN") (pintype "input"))
    )
    (net (code "11") (name "DI8") (class "Default")
      (node (ref "LED7") (pin "1-DOUT") (pinfunction "DO_1-DOUT") (pintype "output"))
      (node (ref "LED8") (pin "3-DIN") (pinfunction "DI_3-DIN") (pintype "input"))
    )
    (net (code "12") (name "DI9") (class "Default")
      (node (ref "LED8") (pin "1-DOUT") (pinfunction "DO_1-DOUT") (pintype "output"))
      (node (ref "LED9") (pin "3-DIN") (pinfunction "DI_3-DIN") (pintype "input"))
    )
    (net (code "13") (name "DI10") (class "Default")
      (node (ref "LED10") (pin "3-DIN") (pinfunction "DI_3-DIN") (pintype "input"))
      (node (ref "LED9") (pin "1-DOUT") (pinfunction "DO_1-DOUT") (pintype "output"))
    )
    (net (code "14") (name "DI11") (class "Default")
      (node (ref "LED10") (pin "1-DOUT") (pinfunction "DO_1-DOUT") (pintype "output"))
      (node (ref "LED11") (pin "3-DIN") (pinfunction "DI_3-DIN") (pintype "input"))
    )
    (net (code "15") (name "DI12") (class "Default")
      (node (ref "LED11") (pin "1-DOUT") (pinfunction "DO_1-DOUT") (pintype "output"))
      (node (ref "LED12") (pin "3-DIN") (pinfunction "DI_3-DIN") (pintype "input"))
    )
    (net (code "16") (name "DI13") (class "Default")
      (node (ref "LED12") (pin "1-DOUT") (pinfunction "DO_1-DOUT") (pintype "output"))
      (node (ref "LED13") (pin "3-DIN") (pinfunction "DI_3-DIN") (pintype "input"))
    )
    (net (code "17") (name "DI14") (class "Default")
      (node (ref "LED13") (pin "1-DOUT") (pinfunction "DO_1-DOUT") (pintype "output"))
      (node (ref "LED14") (pin "3-DIN") (pinfunction "DI_3-DIN") (pintype "input"))
    )
    (net (code "18") (name "DI15") (class "Default")
      (node (ref "LED14") (pin "1-DOUT") (pinfunction "DO_1-DOUT") (pintype "output"))
      (node (ref "LED15") (pin "3-DIN") (pinfunction "DI_3-DIN") (pintype "input"))
    )
    (net (code "19") (name "DI16") (class "Default")
      (node (ref "LED15") (pin "1-DOUT") (pinfunction "DO_1-DOUT") (pintype "output"))
      (node (ref "LED16") (pin "3-DIN") (pinfunction "DI_3-DIN") (pintype "input"))
    )
    (net (code "20") (name "DI17") (class "Default")
      (node (ref "LED16") (pin "1-DOUT") (pinfunction "DO_1-DOUT") (pintype "output"))
      (node (ref "LED17") (pin "3-DIN") (pinfunction "DI_3-DIN") (pintype "input"))
    )
    (net (code "21") (name "DI18") (class "Default")
      (node (ref "LED17") (pin "1-DOUT") (pinfunction "DO_1-DOUT") (pintype "output"))
      (node (ref "LED18") (pin "3-DIN") (pinfunction "DI_3-DIN") (pintype "input"))
    )
    (net (code "22") (name "DI19") (class "Default")
      (node (ref "LED18") (pin "1-DOUT") (pinfunction "DO_1-DOUT") (pintype "output"))
      (node (ref "LED19") (pin "3-DIN") (pinfunction "DI_3-DIN") (pintype "input"))
    )
    (net (code "23") (name "DI20") (class "Default")
      (node (ref "LED19") (pin "1-DOUT") (pinfunction "DO_1-DOUT") (pintype "output"))
      (node (ref "LED20") (pin "3-DIN") (pinfunction "DI_3-DIN") (pintype "input"))
    )
    (net (code "24") (name "DI21") (class "Default")
      (node (ref "LED20") (pin "1-DOUT") (pinfunction "DO_1-DOUT") (pintype "output"))
      (node (ref "LED21") (pin "3-DIN") (pinfunction "DI_3-DIN") (pintype "input"))
    )
    (net (code "25") (name "DI22") (class "Default")
      (node (ref "LED21") (pin "1-DOUT") (pinfunction "DO_1-DOUT") (pintype "output"))
      (node (ref "LED22") (pin "3-DIN") (pinfunction "DI_3-DIN") (pintype "input"))
    )
    (net (code "26") (name "DI23") (class "Default")
      (node (ref "LED22") (pin "1-DOUT") (pinfunction "DO_1-DOUT") (pintype "output"))
      (node (ref "LED23") (pin "3-DIN") (pinfunction "DI_3-DIN") (pintype "input"))
    )
    (net (code "27") (name "DI24") (class "Default")
      (node (ref "LED23") (pin "1-DOUT") (pinfunction "DO_1-DOUT") (pintype "output"))
      (node (ref "LED24") (pin "3-DIN") (pinfunction "DI_3-DIN") (pintype "input"))
    )
    (net (code "28") (name "DI25") (class "Default")
      (node (ref "LED24") (pin "1-DOUT") (pinfunction "DO_1-DOUT") (pintype "output"))
      (node (ref "LED25") (pin "3-DIN") (pinfunction "DI_3-DIN") (pintype "input"))
    )
    (net (code "29") (name "DI26") (class "Default")
      (node (ref "LED25") (pin "1-DOUT") (pinfunction "DO_1-DOUT") (pintype "output"))
      (node (ref "LED26") (pin "3-DIN") (pinfunction "DI_3-DIN") (pintype "input"))
    )
    (net (code "30") (name "DI27") (class "Default")
      (node (ref "LED26") (pin "1-DOUT") (pinfunction "DO_1-DOUT") (pintype "output"))
      (node (ref "LED27") (pin "3-DIN") (pinfunction "DI_3-DIN") (pintype "input"))
    )
    (net (code "31") (name "DI28") (class "Default")
      (node (ref "LED27") (pin "1-DOUT") (pinfunction "DO_1-DOUT") (pintype "output"))
      (node (ref "LED28") (pin "3-DIN") (pinfunction "DI_3-DIN") (pintype "input"))
    )
    (net (code "32") (name "DI29") (class "Default")
      (node (ref "LED28") (pin "1-DOUT") (pinfunction "DO_1-DOUT") (pintype "output"))
      (node (ref "LED29") (pin "3-DIN") (pinfunction "DI_3-DIN") (pintype "input"))
    )
    (net (code "33") (name "DI30") (class "Default")
      (node (ref "LED29") (pin "1-DOUT") (pinfunction "DO_1-DOUT") (pintype "output"))
      (node (ref "LED30") (pin "3-DIN") (pinfunction "DI_3-DIN") (pintype "input"))
    )
    (net (code "34") (name "DI31") (class "Default")
      (node (ref "LED30") (pin "1-DOUT") (pinfunction "DO_1-DOUT") (pintype "output"))
      (node (ref "LED31") (pin "3-DIN") (pinfunction "DI_3-DIN") (pintype "input"))
    )
    (net (code "35") (name "DI32") (class "Default")
      (node (ref "LED31") (pin "1-DOUT") (pinfunction "DO_1-DOUT") (pintype "output"))
      (node (ref "LED32") (pin "3-DIN") (pinfunction "DI_3-DIN") (pintype "input"))
    )
    (net (code "36") (name "DI33") (class "Default")
      (node (ref "LED32") (pin "1-DOUT") (pinfunction "DO_1-DOUT") (pintype "output"))
      (node (ref "LED33") (pin "3-DIN") (pinfunction "DI_3-DIN") (pintype "input"))
    )
    (net (code "37") (name "DI34") (class "Default")
      (node (ref "LED33") (pin "1-DOUT") (pinfunction "DO_1-DOUT") (pintype "output"))
      (node (ref "LED34") (pin "3-DIN") (pinfunction "DI_3-DIN") (pintype "input"))
    )
    (net (code "38") (name "DI35") (class "Default")
      (node (ref "LED34") (pin "1-DOUT") (pinfunction "DO_1-DOUT") (pintype "output"))
      (node (ref "LED35") (pin "3-DIN") (pinfunction "DI_3-DIN") (pintype "input"))
    )
    (net (code "39") (name "DI36") (class "Default")
      (node (ref "LED35") (pin "1-DOUT") (pinfunction "DO_1-DOUT") (pintype "output"))
      (node (ref "LED36") (pin "3-DIN") (pinfunction "DI_3-DIN") (pintype "input"))
    )
    (net (code "40") (name "DI37") (class "Default")
      (node (ref "LED36") (pin "1-DOUT") (pinfunction "DO_1-DOUT") (pintype "output"))
      (node (ref "LED37") (pin "3-DIN") (pinfunction "DI_3-DIN") (pintype "input"))
    )
    (net (code "41") (name "DI38") (class "Default")
      (node (ref "LED37") (pin "1-DOUT") (pinfunction "DO_1-DOUT") (pintype "output"))
      (node (ref "LED38") (pin "3-DIN") (pinfunction "DI_3-DIN") (pintype "input"))
    )
    (net (code "42") (name "DI39") (class "Default")
      (node (ref "LED38") (pin "1-DOUT") (pinfunction "DO_1-DOUT") (pintype "output"))
      (node (ref "LED39") (pin "3-DIN") (pinfunction "DI_3-DIN") (pintype "input"))
    )
    (net (code "43") (name "DI40") (class "Default")
      (node (ref "LED39") (pin "1-DOUT") (pinfunction "DO_1-DOUT") (pintype "output"))
      (node (ref "LED40") (pin "3-DIN") (pinfunction "DI_3-DIN") (pintype "input"))
    )
    (net (code "44") (name "DI41") (class "Default")
      (node (ref "LED40") (pin "1-DOUT") (pinfunction "DO_1-DOUT") (pintype "output"))
      (node (ref "LED41") (pin "3-DIN") (pinfunction "DI_3-DIN") (pintype "input"))
    )
    (net (code "45") (name "DI42") (class "Default")
      (node (ref "LED41") (pin "1-DOUT") (pinfunction "DO_1-DOUT") (pintype "output"))
      (node (ref "LED42") (pin "3-DIN") (pinfunction "DI_3-DIN") (pintype "input"))
    )
    (net (code "46") (name "DI43") (class "Default")
      (node (ref "LED42") (pin "1-DOUT") (pinfunction "DO_1-DOUT") (pintype "output"))
      (node (ref "LED43") (pin "3-DIN") (pinfunction "DI_3-DIN") (pintype "input"))
    )
    (net (code "47") (name "DI44") (class "Default")
      (node (ref "LED43") (pin "1-DOUT") (pinfunction "DO_1-DOUT") (pintype "output"))
      (node (ref "LED44") (pin "3-DIN") (pinfunction "DI_3-DIN") (pintype "input"))
    )
    (net (code "48") (name "DI45") (class "Default")
      (node (ref "LED44") (pin "1-DOUT") (pinfunction "DO_1-DOUT") (pintype "output"))
      (node (ref "LED45") (pin "3-DIN") (pinfunction "DI_3-DIN") (pintype "input"))
    )
    (net (code "49") (name "DI46") (class "Default")
      (node (ref "LED45") (pin "1-DOUT") (pinfunction "DO_1-DOUT") (pintype "output"))
      (node (ref "LED46") (pin "3-DIN") (pinfunction "DI_3-DIN") (pintype "input"))
    )
    (net (code "50") (name "DI47") (class "Default")
      (node (ref "LED46") (pin "1-DOUT") (pinfunction "DO_1-DOUT") (pintype "output"))
      (node (ref "LED47") (pin "3-DIN") (pinfunction "DI_3-DIN") (pintype "input"))
    )
    (net (code "51") (name "DI48") (class "Default")
      (node (ref "LED47") (pin "1-DOUT") (pinfunction "DO_1-DOUT") (pintype "output"))
      (node (ref "LED48") (pin "3-DIN") (pinfunction "DI_3-DIN") (pintype "input"))
    )
    (net (code "52") (name "DI49") (class "Default")
      (node (ref "LED48") (pin "1-DOUT") (pinfunction "DO_1-DOUT") (pintype "output"))
      (node (ref "LED49") (pin "3-DIN") (pinfunction "DI_3-DIN") (pintype "input"))
    )
    (net (code "53") (name "DI50") (class "Default")
      (node (ref "LED49") (pin "1-DOUT") (pinfunction "DO_1-DOUT") (pintype "output"))
      (node (ref "LED50") (pin "3-DIN") (pinfunction "DI_3-DIN") (pintype "input"))
    )
    (net (code "54") (name "DI51") (class "Default")
      (node (ref "LED50") (pin "1-DOUT") (pinfunction "DO_1-DOUT") (pintype "output"))
      (node (ref "LED51") (pin "3-DIN") (pinfunction "DI_3-DIN") (pintype "input"))
    )
    (net (code "55") (name "DI52") (class "Default")
      (node (ref "LED51") (pin "1-DOUT") (pinfunction "DO_1-DOUT") (pintype "output"))
      (node (ref "LED52") (pin "3-DIN") (pinfunction "DI_3-DIN") (pintype "input"))
    )
    (net (code "56") (name "DI53") (class "Default")
      (node (ref "LED52") (pin "1-DOUT") (pinfunction "DO_1-DOUT") (pintype "output"))
      (node (ref "LED53") (pin "3-DIN") (pinfunction "DI_3-DIN") (pintype "input"))
    )
    (net (code "57") (name "DI54") (class "Default")
      (node (ref "LED53") (pin "1-DOUT") (pinfunction "DO_1-DOUT") (pintype "output"))
      (node (ref "LED54") (pin "3-DIN") (pinfunction "DI_3-DIN") (pintype "input"))
    )
    (net (code "58") (name "DI55") (class "Default")
      (node (ref "LED54") (pin "1-DOUT") (pinfunction "DO_1-DOUT") (pintype "output"))
      (node (ref "LED55") (pin "3-DIN") (pinfunction "DI_3-DIN") (pintype "input"))
    )
    (net (code "59") (name "DI56") (class "Default")
      (node (ref "LED55") (pin "1-DOUT") (pinfunction "DO_1-DOUT") (pintype "output"))
      (node (ref "LED56") (pin "3-DIN") (pinfunction "DI_3-DIN") (pintype "input"))
    )
    (net (code "60") (name "DI57") (class "Default")
      (node (ref "LED56") (pin "1-DOUT") (pinfunction "DO_1-DOUT") (pintype "output"))
      (node (ref "LED57") (pin "3-DIN") (pinfunction "DI_3-DIN") (pintype "input"))
    )
    (net (code "61") (name "DI58") (class "Default")
      (node (ref "LED57") (pin "1-DOUT") (pinfunction "DO_1-DOUT") (pintype "output"))
      (node (ref "LED58") (pin "3-DIN") (pinfunction "DI_3-DIN") (pintype "input"))
    )
    (net (code "62") (name "DI59") (class "Default")
      (node (ref "LED58") (pin "1-DOUT") (pinfunction "DO_1-DOUT") (pintype "output"))
      (node (ref "LED59") (pin "3-DIN") (pinfunction "DI_3-DIN") (pintype "input"))
    )
    (net (code "63") (name "DI60") (class "Default")
      (node (ref "LED59") (pin "1-DOUT") (pinfunction "DO_1-DOUT") (pintype "output"))
      (node (ref "LED60") (pin "3-DIN") (pinfunction "DI_3-DIN") (pintype "input"))
    )
    (net (code "64") (name "DI61") (class "Default")
      (node (ref "LED60") (pin "1-DOUT") (pinfunction "DO_1-DOUT") (pintype "output"))
      (node (ref "LED61") (pin "3-DIN") (pinfunction "DI_3-DIN") (pintype "input"))
    )
    (net (code "65") (name "DI62") (class "Default")
      (node (ref "LED61") (pin "1-DOUT") (pinfunction "DO_1-DOUT") (pintype "output"))
      (node (ref "LED62") (pin "3-DIN") (pinfunction "DI_3-DIN") (pintype "input"))
    )
    (net (code "66") (name "DI63") (class "Default")
      (node (ref "LED62") (pin "1-DOUT") (pinfunction "DO_1-DOUT") (pintype "output"))
      (node (ref "LED63") (pin "3-DIN") (pinfunction "DI_3-DIN") (pintype "input"))
    )
    (net (code "67") (name "DI64") (class "Default")
      (node (ref "LED63") (pin "1-DOUT") (pinfunction "DO_1-DOUT") (pintype "output"))
      (node (ref "LED64") (pin "3-DIN") (pinfunction "DI_3-DIN") (pintype "input"))
    )
    (net (code "68") (name "DI65") (class "Default")
      (node (ref "LED64") (pin "1-DOUT") (pinfunction "DO_1-DOUT") (pintype "output"))
      (node (ref "LED65") (pin "3-DIN") (pinfunction "DI_3-DIN") (pintype "input"))
    )
    (net (code "69") (name "DI66") (class "Default")
      (node (ref "LED65") (pin "1-DOUT") (pinfunction "DO_1-DOUT") (pintype "output"))
      (node (ref "LED66") (pin "3-DIN") (pinfunction "DI_3-DIN") (pintype "input"))
    )
    (net (code "70") (name "DI67") (class "Default")
      (node (ref "LED66") (pin "1-DOUT") (pinfunction "DO_1-DOUT") (pintype "output"))
      (node (ref "LED67") (pin "3-DIN") (pinfunction "DI_3-DIN") (pintype "input"))
    )
    (net (code "71") (name "DI68") (class "Default")
      (node (ref "LED67") (pin "1-DOUT") (pinfunction "DO_1-DOUT") (pintype "output"))
      (node (ref "LED68") (pin "3-DIN") (pinfunction "DI_3-DIN") (pintype "input"))
    )
    (net (code "72") (name "DI69") (class "Default")
      (node (ref "LED68") (pin "1-DOUT") (pinfunction "DO_1-DOUT") (pintype "output"))
      (node (ref "LED69") (pin "3-DIN") (pinfunction "DI_3-DIN") (pintype "input"))
    )
    (net (code "73") (name "DI70") (class "Default")
      (node (ref "LED69") (pin "1-DOUT") (pinfunction "DO_1-DOUT") (pintype "output"))
      (node (ref "LED70") (pin "3-DIN") (pinfunction "DI_3-DIN") (pintype "input"))
    )
    (net (code "74") (name "DI71") (class "Default")
      (node (ref "LED70") (pin "1-DOUT") (pinfunction "DO_1-DOUT") (pintype "output"))
      (node (ref "LED71") (pin "3-DIN") (pinfunction "DI_3-DIN") (pintype "input"))
    )
    (net (code "75") (name "DI72") (class "Default")
      (node (ref "LED71") (pin "1-DOUT") (pinfunction "DO_1-DOUT") (pintype "output"))
      (node (ref "LED72") (pin "3-DIN") (pinfunction "DI_3-DIN") (pintype "input"))
    )
    (net (code "76") (name "DI73") (class "Default")
      (node (ref "LED72") (pin "1-DOUT") (pinfunction "DO_1-DOUT") (pintype "output"))
      (node (ref "LED73") (pin "3-DIN") (pinfunction "DI_3-DIN") (pintype "input"))
    )
    (net (code "77") (name "DI74") (class "Default")
      (node (ref "LED73") (pin "1-DOUT") (pinfunction "DO_1-DOUT") (pintype "output"))
      (node (ref "LED74") (pin "3-DIN") (pinfunction "DI_3-DIN") (pintype "input"))
    )
    (net (code "78") (name "DI75") (class "Default")
      (node (ref "LED74") (pin "1-DOUT") (pinfunction "DO_1-DOUT") (pintype "output"))
      (node (ref "LED75") (pin "3-DIN") (pinfunction "DI_3-DIN") (pintype "input"))
    )
    (net (code "79") (name "DI76") (class "Default")
      (node (ref "LED75") (pin "1-DOUT") (pinfunction "DO_1-DOUT") (pintype "output"))
      (node (ref "LED76") (pin "3-DIN") (pinfunction "DI_3-DIN") (pintype "input"))
    )
    (net (code "80") (name "DI77") (class "Default")
      (node (ref "LED76") (pin "1-DOUT") (pinfunction "DO_1-DOUT") (pintype "output"))
      (node (ref "LED77") (pin "3-DIN") (pinfunction "DI_3-DIN") (pintype "input"))
    )
    (net (code "81") (name "DI78") (class "Default")
      (node (ref "LED77") (pin "1-DOUT") (pinfunction "DO_1-DOUT") (pintype "output"))
      (node (ref "LED78") (pin "3-DIN") (pinfunction "DI_3-DIN") (pintype "input"))
    )
    (net (code "82") (name "DI79") (class "Default")
      (node (ref "LED78") (pin "1-DOUT") (pinfunction "DO_1-DOUT") (pintype "output"))
      (node (ref "LED79") (pin "3-DIN") (pinfunction "DI_3-DIN") (pintype "input"))
    )
    (net (code "83") (name "DI80") (class "Default")
      (node (ref "LED79") (pin "1-DOUT") (pinfunction "DO_1-DOUT") (pintype "output"))
      (node (ref "LED80") (pin "3-DIN") (pinfunction "DI_3-DIN") (pintype "input"))
    )
    (net (code "84") (name "DI81") (class "Default")
      (node (ref "LED80") (pin "1-DOUT") (pinfunction "DO_1-DOUT") (pintype "output"))
      (node (ref "LED81") (pin "3-DIN") (pinfunction "DI_3-DIN") (pintype "input"))
    )
    (net (code "85") (name "DI82") (class "Default")
      (node (ref "LED81") (pin "1-DOUT") (pinfunction "DO_1-DOUT") (pintype "output"))
      (node (ref "LED82") (pin "3-DIN") (pinfunction "DI_3-DIN") (pintype "input"))
    )
    (net (code "86") (name "DI83") (class "Default")
      (node (ref "LED82") (pin "1-DOUT") (pinfunction "DO_1-DOUT") (pintype "output"))
      (node (ref "LED83") (pin "3-DIN") (pinfunction "DI_3-DIN") (pintype "input"))
    )
    (net (code "87") (name "DI84") (class "Default")
      (node (ref "LED83") (pin "1-DOUT") (pinfunction "DO_1-DOUT") (pintype "output"))
      (node (ref "LED84") (pin "3-DIN") (pinfunction "DI_3-DIN") (pintype "input"))
    )
    (net (code "88") (name "DI85") (class "Default")
      (node (ref "LED84") (pin "1-DOUT") (pinfunction "DO_1-DOUT") (pintype "output"))
      (node (ref "LED85") (pin "3-DIN") (pinfunction "DI_3-DIN") (pintype "input"))
    )
    (net (code "89") (name "DI86") (class "Default")
      (node (ref "LED85") (pin "1-DOUT") (pinfunction "DO_1-DOUT") (pintype "output"))
      (node (ref "LED86") (pin "3-DIN") (pinfunction "DI_3-DIN") (pintype "input"))
    )
    (net (code "90") (name "DI87") (class "Default")
      (node (ref "LED86") (pin "1-DOUT") (pinfunction "DO_1-DOUT") (pintype "output"))
      (node (ref "LED87") (pin "3-DIN") (pinfunction "DI_3-DIN") (pintype "input"))
    )
    (net (code "91") (name "DI88") (class "Default")
      (node (ref "LED87") (pin "1-DOUT") (pinfunction "DO_1-DOUT") (pintype "output"))
      (node (ref "LED88") (pin "3-DIN") (pinfunction "DI_3-DIN") (pintype "input"))
    )
    (net (code "92") (name "DI89") (class "Default")
      (node (ref "LED88") (pin "1-DOUT") (pinfunction "DO_1-DOUT") (pintype "output"))
      (node (ref "LED89") (pin "3-DIN") (pinfunction "DI_3-DIN") (pintype "input"))
    )
    (net (code "93") (name "DI90") (class "Default")
      (node (ref "LED89") (pin "1-DOUT") (pinfunction "DO_1-DOUT") (pintype "output"))
      (node (ref "LED90") (pin "3-DIN") (pinfunction "DI_3-DIN") (pintype "input"))
    )
    (net (code "94") (name "DI91") (class "Default")
      (node (ref "LED90") (pin "1-DOUT") (pinfunction "DO_1-DOUT") (pintype "output"))
      (node (ref "LED91") (pin "3-DIN") (pinfunction "DI_3-DIN") (pintype "input"))
    )
    (net (code "95") (name "DI92") (class "Default")
      (node (ref "LED91") (pin "1-DOUT") (pinfunction "DO_1-DOUT") (pintype "output"))
      (node (ref "LED92") (pin "3-DIN") (pinfunction "DI_3-DIN") (pintype "input"))
    )
    (net (code "96") (name "DI93") (class "Default")
      (node (ref "LED92") (pin "1-DOUT") (pinfunction "DO_1-DOUT") (pintype "output"))
      (node (ref "LED93") (pin "3-DIN") (pinfunction "DI_3-DIN") (pintype "input"))
    )
    (net (code "97") (name "DI94") (class "Default")
      (node (ref "LED93") (pin "1-DOUT") (pinfunction "DO_1-DOUT") (pintype "output"))
      (node (ref "LED94") (pin "3-DIN") (pinfunction "DI_3-DIN") (pintype "input"))
    )
    (net (code "98") (name "DI95") (class "Default")
      (node (ref "LED94") (pin "1-DOUT") (pinfunction "DO_1-DOUT") (pintype "output"))
      (node (ref "LED95") (pin "3-DIN") (pinfunction "DI_3-DIN") (pintype "input"))
    )
    (net (code "99") (name "DI96") (class "Default")
      (node (ref "LED95") (pin "1-DOUT") (pinfunction "DO_1-DOUT") (pintype "output"))
      (node (ref "LED96") (pin "3-DIN") (pinfunction "DI_3-DIN") (pintype "input"))
    )
    (net (code "100") (name "DI97") (class "Default")
      (node (ref "LED96") (pin "1-DOUT") (pinfunction "DO_1-DOUT") (pintype "output"))
      (node (ref "LED97") (pin "3-DIN") (pinfunction "DI_3-DIN") (pintype "input"))
    )
    (net (code "101") (name "DI98") (class "Default")
      (node (ref "LED97") (pin "1-DOUT") (pinfunction "DO_1-DOUT") (pintype "output"))
      (node (ref "LED98") (pin "3-DIN") (pinfunction "DI_3-DIN") (pintype "input"))
    )
    (net (code "102") (name "DI99") (class "Default")
      (node (ref "LED98") (pin "1-DOUT") (pinfunction "DO_1-DOUT") (pintype "output"))
      (node (ref "LED99") (pin "3-DIN") (pinfunction "DI_3-DIN") (pintype "input"))
    )
    (net (code "103") (name "DI100") (class "Default")
      (node (ref "LED100") (pin "3-DIN") (pinfunction "DI_3-DIN") (pintype "input"))
      (node (ref "LED99") (pin "1-DOUT") (pinfunction "DO_1-DOUT") (pintype "output"))
    )
    (net (code "104") (name "DI101") (class "Default")
      (node (ref "LED100") (pin "1-DOUT") (pinfunction "DO_1-DOUT") (pintype "output"))
      (node (ref "LED101") (pin "3-DIN") (pinfunction "DI_3-DIN") (pintype "input"))
    )
    (net (code "105") (name "DI102") (class "Default")
      (node (ref "LED101") (pin "1-DOUT") (pinfunction "DO_1-DOUT") (pintype "output"))
      (node (ref "LED102") (pin "3-DIN") (pinfunction "DI_3-DIN") (pintype "input"))
    )
    (net (code "106") (name "DI103") (class "Default")
      (node (ref "LED102") (pin "1-DOUT") (pinfunction "DO_1-DOUT") (pintype "output"))
      (node (ref "LED103") (pin "3-DIN") (pinfunction "DI_3-DIN") (pintype "input"))
    )
    (net (code "107") (name "DI104") (class "Default")
      (node (ref "LED103") (pin "1-DOUT") (pinfunction "DO_1-DOUT") (pintype "output"))
      (node (ref "LED104") (pin "3-DIN") (pinfunction "DI_3-DIN") (pintype "input"))
    )
    (net (code "108") (name "DI105") (class "Default")
      (node (ref "LED104") (pin "1-DOUT") (pinfunction "DO_1-DOUT") (pintype "output"))
      (node (ref "LED105") (pin "3-DIN") (pinfunction "DI_3-DIN") (pintype "input"))
    )
    (net (code "109") (name "DO") (class "Default")
      (node (ref "JP1") (pin "1") (pinfunction "1_1") (pintype "passive"))
      (node (ref "LED105") (pin "1-DOUT") (pinfunction "DO_1-DOUT") (pintype "output"))
    )
    (net (code "110") (name "GND") (class "Default")
      (node (ref "C1") (pin "1") (pinfunction "1_1") (pintype "passive"))
      (node (ref "C2") (pin "1") (pinfunction "1_1") (pintype "passive"))
      (node (ref "C3") (pin "P$2") (pinfunction "2_P$2") (pintype "passive"))
      (node (ref "C4") (pin "P$2") (pinfunction "2_P$2") (pintype "passive"))
      (node (ref "C5") (pin "2") (pinfunction "2_2") (pintype "passive"))
      (node (ref "C6") (pin "2") (pinfunction "2_2") (pintype "passive"))
      (node (ref "C7") (pin "2") (pinfunction "2_2") (pintype "passive"))
      (node (ref "C8") (pin "2") (pinfunction "2_2") (pintype "passive"))
      (node (ref "C9") (pin "2") (pinfunction "2_2") (pintype "passive"))
      (node (ref "CON1") (pin "A1") (pinfunction "GND_A1") (pintype "passive"))
      (node (ref "CON1") (pin "A12") (pinfunction "GND1_A12") (pintype "passive"))
      (node (ref "CON1") (pin "B1") (pinfunction "GND3_B1") (pintype "passive"))
      (node (ref "CON1") (pin "B12") (pinfunction "GND2_B12") (pintype "passive"))
      (node (ref "CON1") (pin "P$1") (pinfunction "SHIELD_P$1") (pintype "passive"))
      (node (ref "CON1") (pin "P$2") (pinfunction "SHIELD_P$2") (pintype "passive"))
      (node (ref "CON1") (pin "P$3") (pinfunction "SHIELD_P$3") (pintype "passive"))
      (node (ref "CON1") (pin "P$4") (pinfunction "SHIELD_P$4") (pintype "passive"))
      (node (ref "D1") (pin "1") (pinfunction "-_1") (pintype "passive"))
      (node (ref "D3") (pin "2") (pinfunction "GND_2") (pintype "passive"))
      (node (ref "LED1") (pin "4-GND") (pinfunction "GND_4-GND") (pintype "power_in"))
      (node (ref "LED10") (pin "4-GND") (pinfunction "GND_4-GND") (pintype "power_in"))
      (node (ref "LED100") (pin "4-GND") (pinfunction "GND_4-GND") (pintype "power_in"))
      (node (ref "LED101") (pin "4-GND") (pinfunction "GND_4-GND") (pintype "power_in"))
      (node (ref "LED102") (pin "4-GND") (pinfunction "GND_4-GND") (pintype "power_in"))
      (node (ref "LED103") (pin "4-GND") (pinfunction "GND_4-GND") (pintype "power_in"))
      (node (ref "LED104") (pin "4-GND") (pinfunction "GND_4-GND") (pintype "power_in"))
      (node (ref "LED105") (pin "4-GND") (pinfunction "GND_4-GND") (pintype "power_in"))
      (node (ref "LED11") (pin "4-GND") (pinfunction "GND_4-GND") (pintype "power_in"))
      (node (ref "LED12") (pin "4-GND") (pinfunction "GND_4-GND") (pintype "power_in"))
      (node (ref "LED13") (pin "4-GND") (pinfunction "GND_4-GND") (pintype "power_in"))
      (node (ref "LED14") (pin "4-GND") (pinfunction "GND_4-GND") (pintype "power_in"))
      (node (ref "LED15") (pin "4-GND") (pinfunction "GND_4-GND") (pintype "power_in"))
      (node (ref "LED16") (pin "4-GND") (pinfunction "GND_4-GND") (pintype "power_in"))
      (node (ref "LED17") (pin "4-GND") (pinfunction "GND_4-GND") (pintype "power_in"))
      (node (ref "LED18") (pin "4-GND") (pinfunction "GND_4-GND") (pintype "power_in"))
      (node (ref "LED19") (pin "4-GND") (pinfunction "GND_4-GND") (pintype "power_in"))
      (node (ref "LED2") (pin "4-GND") (pinfunction "GND_4-GND") (pintype "power_in"))
      (node (ref "LED20") (pin "4-GND") (pinfunction "GND_4-GND") (pintype "power_in"))
      (node (ref "LED21") (pin "4-GND") (pinfunction "GND_4-GND") (pintype "power_in"))
      (node (ref "LED22") (pin "4-GND") (pinfunction "GND_4-GND") (pintype "power_in"))
      (node (ref "LED23") (pin "4-GND") (pinfunction "GND_4-GND") (pintype "power_in"))
      (node (ref "LED24") (pin "4-GND") (pinfunction "GND_4-GND") (pintype "power_in"))
      (node (ref "LED25") (pin "4-GND") (pinfunction "GND_4-GND") (pintype "power_in"))
      (node (ref "LED26") (pin "4-GND") (pinfunction "GND_4-GND") (pintype "power_in"))
      (node (ref "LED27") (pin "4-GND") (pinfunction "GND_4-GND") (pintype "power_in"))
      (node (ref "LED28") (pin "4-GND") (pinfunction "GND_4-GND") (pintype "power_in"))
      (node (ref "LED29") (pin "4-GND") (pinfunction "GND_4-GND") (pintype "power_in"))
      (node (ref "LED3") (pin "4-GND") (pinfunction "GND_4-GND") (pintype "power_in"))
      (node (ref "LED30") (pin "4-GND") (pinfunction "GND_4-GND") (pintype "power_in"))
      (node (ref "LED31") (pin "4-GND") (pinfunction "GND_4-GND") (pintype "power_in"))
      (node (ref "LED32") (pin "4-GND") (pinfunction "GND_4-GND") (pintype "power_in"))
      (node (ref "LED33") (pin "4-GND") (pinfunction "GND_4-GND") (pintype "power_in"))
      (node (ref "LED34") (pin "4-GND") (pinfunction "GND_4-GND") (pintype "power_in"))
      (node (ref "LED35") (pin "4-GND") (pinfunction "GND_4-GND") (pintype "power_in"))
      (node (ref "LED36") (pin "4-GND") (pinfunction "GND_4-GND") (pintype "power_in"))
      (node (ref "LED37") (pin "4-GND") (pinfunction "GND_4-GND") (pintype "power_in"))
      (node (ref "LED38") (pin "4-GND") (pinfunction "GND_4-GND") (pintype "power_in"))
      (node (ref "LED39") (pin "4-GND") (pinfunction "GND_4-GND") (pintype "power_in"))
      (node (ref "LED4") (pin "4-GND") (pinfunction "GND_4-GND") (pintype "power_in"))
      (node (ref "LED40") (pin "4-GND") (pinfunction "GND_4-GND") (pintype "power_in"))
      (node (ref "LED41") (pin "4-GND") (pinfunction "GND_4-GND") (pintype "power_in"))
      (node (ref "LED42") (pin "4-GND") (pinfunction "GND_4-GND") (pintype "power_in"))
      (node (ref "LED43") (pin "4-GND") (pinfunction "GND_4-GND") (pintype "power_in"))
      (node (ref "LED44") (pin "4-GND") (pinfunction "GND_4-GND") (pintype "power_in"))
      (node (ref "LED45") (pin "4-GND") (pinfunction "GND_4-GND") (pintype "power_in"))
      (node (ref "LED46") (pin "4-GND") (pinfunction "GND_4-GND") (pintype "power_in"))
      (node (ref "LED47") (pin "4-GND") (pinfunction "GND_4-GND") (pintype "power_in"))
      (node (ref "LED48") (pin "4-GND") (pinfunction "GND_4-GND") (pintype "power_in"))
      (node (ref "LED49") (pin "4-GND") (pinfunction "GND_4-GND") (pintype "power_in"))
      (node (ref "LED5") (pin "4-GND") (pinfunction "GND_4-GND") (pintype "power_in"))
      (node (ref "LED50") (pin "4-GND") (pinfunction "GND_4-GND") (pintype "power_in"))
      (node (ref "LED51") (pin "4-GND") (pinfunction "GND_4-GND") (pintype "power_in"))
      (node (ref "LED52") (pin "4-GND") (pinfunction "GND_4-GND") (pintype "power_in"))
      (node (ref "LED53") (pin "4-GND") (pinfunction "GND_4-GND") (pintype "power_in"))
      (node (ref "LED54") (pin "4-GND") (pinfunction "GND_4-GND") (pintype "power_in"))
      (node (ref "LED55") (pin "4-GND") (pinfunction "GND_4-GND") (pintype "power_in"))
      (node (ref "LED56") (pin "4-GND") (pinfunction "GND_4-GND") (pintype "power_in"))
      (node (ref "LED57") (pin "4-GND") (pinfunction "GND_4-GND") (pintype "power_in"))
      (node (ref "LED58") (pin "4-GND") (pinfunction "GND_4-GND") (pintype "power_in"))
      (node (ref "LED59") (pin "4-GND") (pinfunction "GND_4-GND") (pintype "power_in"))
      (node (ref "LED6") (pin "4-GND") (pinfunction "GND_4-GND") (pintype "power_in"))
      (node (ref "LED60") (pin "4-GND") (pinfunction "GND_4-GND") (pintype "power_in"))
      (node (ref "LED61") (pin "4-GND") (pinfunction "GND_4-GND") (pintype "power_in"))
      (node (ref "LED62") (pin "4-GND") (pinfunction "GND_4-GND") (pintype "power_in"))
      (node (ref "LED63") (pin "4-GND") (pinfunction "GND_4-GND") (pintype "power_in"))
      (node (ref "LED64") (pin "4-GND") (pinfunction "GND_4-GND") (pintype "power_in"))
      (node (ref "LED65") (pin "4-GND") (pinfunction "GND_4-GND") (pintype "power_in"))
      (node (ref "LED66") (pin "4-GND") (pinfunction "GND_4-GND") (pintype "power_in"))
      (node (ref "LED67") (pin "4-GND") (pinfunction "GND_4-GND") (pintype "power_in"))
      (node (ref "LED68") (pin "4-GND") (pinfunction "GND_4-GND") (pintype "power_in"))
      (node (ref "LED69") (pin "4-GND") (pinfunction "GND_4-GND") (pintype "power_in"))
      (node (ref "LED7") (pin "4-GND") (pinfunction "GND_4-GND") (pintype "power_in"))
      (node (ref "LED70") (pin "4-GND") (pinfunction "GND_4-GND") (pintype "power_in"))
      (node (ref "LED71") (pin "4-GND") (pinfunction "GND_4-GND") (pintype "power_in"))
      (node (ref "LED72") (pin "4-GND") (pinfunction "GND_4-GND") (pintype "power_in"))
      (node (ref "LED73") (pin "4-GND") (pinfunction "GND_4-GND") (pintype "power_in"))
      (node (ref "LED74") (pin "4-GND") (pinfunction "GND_4-GND") (pintype "power_in"))
      (node (ref "LED75") (pin "4-GND") (pinfunction "GND_4-GND") (pintype "power_in"))
      (node (ref "LED76") (pin "4-GND") (pinfunction "GND_4-GND") (pintype "power_in"))
      (node (ref "LED77") (pin "4-GND") (pinfunction "GND_4-GND") (pintype "power_in"))
      (node (ref "LED78") (pin "4-GND") (pinfunction "GND_4-GND") (pintype "power_in"))
      (node (ref "LED79") (pin "4-GND") (pinfunction "GND_4-GND") (pintype "power_in"))
      (node (ref "LED8") (pin "4-GND") (pinfunction "GND_4-GND") (pintype "power_in"))
      (node (ref "LED80") (pin "4-GND") (pinfunction "GND_4-GND") (pintype "power_in"))
      (node (ref "LED81") (pin "4-GND") (pinfunction "GND_4-GND") (pintype "power_in"))
      (node (ref "LED82") (pin "4-GND") (pinfunction "GND_4-GND") (pintype "power_in"))
      (node (ref "LED83") (pin "4-GND") (pinfunction "GND_4-GND") (pintype "power_in"))
      (node (ref "LED84") (pin "4-GND") (pinfunction "GND_4-GND") (pintype "power_in"))
      (node (ref "LED85") (pin "4-GND") (pinfunction "GND_4-GND") (pintype "power_in"))
      (node (ref "LED86") (pin "4-GND") (pinfunction "GND_4-GND") (pintype "power_in"))
      (node (ref "LED87") (pin "4-GND") (pinfunction "GND_4-GND") (pintype "power_in"))
      (node (ref "LED88") (pin "4-GND") (pinfunction "GND_4-GND") (pintype "power_in"))
      (node (ref "LED89") (pin "4-GND") (pinfunction "GND_4-GND") (pintype "power_in"))
      (node (ref "LED9") (pin "4-GND") (pinfunction "GND_4-GND") (pintype "power_in"))
      (node (ref "LED90") (pin "4-GND") (pinfunction "GND_4-GND") (pintype "power_in"))
      (node (ref "LED91") (pin "4-GND") (pinfunction "GND_4-GND") (pintype "power_in"))
      (node (ref "LED92") (pin "4-GND") (pinfunction "GND_4-GND") (pintype "power_in"))
      (node (ref "LED93") (pin "4-GND") (pinfunction "GND_4-GND") (pintype "power_in"))
      (node (ref "LED94") (pin "4-GND") (pinfunction "GND_4-GND") (pintype "power_in"))
      (node (ref "LED95") (pin "4-GND") (pinfunction "GND_4-GND") (pintype "power_in"))
      (node (ref "LED96") (pin "4-GND") (pinfunction "GND_4-GND") (pintype "power_in"))
      (node (ref "LED97") (pin "4-GND") (pinfunction "GND_4-GND") (pintype "power_in"))
      (node (ref "LED98") (pin "4-GND") (pinfunction "GND_4-GND") (pintype "power_in"))
      (node (ref "LED99") (pin "4-GND") (pinfunction "GND_4-GND") (pintype "power_in"))
      (node (ref "MS1") (pin "4") (pinfunction "GND_4") (pintype "power_in"))
      (node (ref "R1") (pin "1") (pinfunction "1_1") (pintype "passive"))
      (node (ref "R2") (pin "2") (pinfunction "2_2") (pintype "passive"))
      (node (ref "S1") (pin "3") (pinfunction "3_3") (pintype "passive"))
      (node (ref "S1") (pin "4") (pinfunction "4_4") (pintype "passive"))
      (node (ref "S1") (pin "5") (pinfunction "4_5") (pintype "passive"))
      (node (ref "S1") (pin "6") (pinfunction "3_6") (pintype "passive"))
      (node (ref "S2") (pin "3") (pinfunction "3_3") (pintype "passive"))
      (node (ref "S2") (pin "4") (pinfunction "4_4") (pintype "passive"))
      (node (ref "S2") (pin "5") (pinfunction "4_5") (pintype "passive"))
      (node (ref "S2") (pin "6") (pinfunction "3_6") (pintype "passive"))
      (node (ref "ST2") (pin "1") (pinfunction "1_1") (pintype "bidirectional"))
      (node (ref "U$1") (pin "2") (pinfunction "GND_2") (pintype "input"))
    )
    (net (code "111") (name "Net-(CON1-CC1)") (class "Default")
      (node (ref "CON1") (pin "A5") (pinfunction "CC1_A5") (pintype "passive"))
      (node (ref "R1") (pin "2") (pinfunction "2_2") (pintype "passive"))
    )
    (net (code "112") (name "Net-(CON1-CC2)") (class "Default")
      (node (ref "CON1") (pin "B5") (pinfunction "CC2_B5") (pintype "passive"))
      (node (ref "R2") (pin "1") (pinfunction "1_1") (pintype "passive"))
    )
    (net (code "113") (name "Net-(D1-+)") (class "Default")
      (node (ref "D1") (pin "2") (pinfunction "+_2") (pintype "passive"))
      (node (ref "R6") (pin "1") (pinfunction "1_1") (pintype "passive"))
    )
    (net (code "114") (name "Net-(MS1-GPIO6)") (class "Default")
      (node (ref "MS1") (pin "20") (pinfunction "GPIO6_20") (pintype "bidirectional"))
      (node (ref "R9") (pin "1") (pinfunction "1_1") (pintype "passive"))
    )
    (net (code "115") (name "Net-(MS1-GPIO12)") (class "Default")
      (node (ref "MS1") (pin "24") (pinfunction "GPIO12_24") (pintype "bidirectional"))
      (node (ref "R4") (pin "1") (pinfunction "1_1") (pintype "passive"))
    )
    (net (code "116") (name "Net-(MS1-GPIOMOSI)") (class "Default")
      (node (ref "MS1") (pin "12") (pinfunction "GPIOMOSI_12") (pintype "bidirectional"))
      (node (ref "R10") (pin "1") (pinfunction "1_1") (pintype "passive"))
    )
    (net (code "117") (name "Net-(MS1-USB)") (class "Default")
      (node (ref "MS1") (pin "26") (pinfunction "USB_26") (pintype "power_in"))
      (node (ref "R8") (pin "1") (pinfunction "1_1") (pintype "passive"))
    )
    (net (code "118") (name "Net-(U$1-A)") (class "Default")
      (node (ref "R5") (pin "1") (pinfunction "1_1") (pintype "passive"))
      (node (ref "U$1") (pin "3") (pinfunction "A_3") (pintype "open_collector"))
    )
    (net (code "119") (name "Net-(U$1-B)") (class "Default")
      (node (ref "R3") (pin "1") (pinfunction "1_1") (pintype "passive"))
      (node (ref "R7") (pin "1") (pinfunction "1_1") (pintype "passive"))
      (node (ref "U$1") (pin "4") (pinfunction "B_4") (pintype "power_in"))
    )
    (net (code "120") (name "PROG") (class "Default")
      (node (ref "MS1") (pin "19") (pinfunction "GPIO5_19") (pintype "bidirectional"))
      (node (ref "S2") (pin "1") (pinfunction "1_1") (pintype "passive"))
      (node (ref "S2") (pin "2") (pinfunction "2_2") (pintype "passive"))
      (node (ref "S2") (pin "7") (pinfunction "1_7") (pintype "passive"))
      (node (ref "S2") (pin "8") (pinfunction "2_8") (pintype "passive"))
    )
    (net (code "121") (name "VBAT") (class "Default")
      (node (ref "D2") (pin "A") (pinfunction "A_A") (pintype "passive"))
      (node (ref "MS1") (pin "28") (pinfunction "VBAT_28") (pintype "power_in"))
    )
    (net (code "122") (name "VDD") (class "Default")
      (node (ref "C2") (pin "2") (pinfunction "2_2") (pintype "passive"))
      (node (ref "C7") (pin "1") (pinfunction "1_1") (pintype "passive"))
      (node (ref "C8") (pin "1") (pinfunction "1_1") (pintype "passive"))
      (node (ref "C9") (pin "1") (pinfunction "1_1") (pintype "passive"))
      (node (ref "F1") (pin "2") (pinfunction "2_2") (pintype "passive"))
      (node (ref "F2") (pin "2") (pinfunction "2_2") (pintype "passive"))
      (node (ref "LED1") (pin "2-VDD") (pinfunction "VDD_2-VDD") (pintype "power_in"))
      (node (ref "LED10") (pin "2-VDD") (pinfunction "VDD_2-VDD") (pintype "power_in"))
      (node (ref "LED100") (pin "2-VDD") (pinfunction "VDD_2-VDD") (pintype "power_in"))
      (node (ref "LED101") (pin "2-VDD") (pinfunction "VDD_2-VDD") (pintype "power_in"))
      (node (ref "LED102") (pin "2-VDD") (pinfunction "VDD_2-VDD") (pintype "power_in"))
      (node (ref "LED103") (pin "2-VDD") (pinfunction "VDD_2-VDD") (pintype "power_in"))
      (node (ref "LED104") (pin "2-VDD") (pinfunction "VDD_2-VDD") (pintype "power_in"))
      (node (ref "LED105") (pin "2-VDD") (pinfunction "VDD_2-VDD") (pintype "power_in"))
      (node (ref "LED11") (pin "2-VDD") (pinfunction "VDD_2-VDD") (pintype "power_in"))
      (node (ref "LED12") (pin "2-VDD") (pinfunction "VDD_2-VDD") (pintype "power_in"))
      (node (ref "LED13") (pin "2-VDD") (pinfunction "VDD_2-VDD") (pintype "power_in"))
      (node (ref "LED14") (pin "2-VDD") (pinfunction "VDD_2-VDD") (pintype "power_in"))
      (node (ref "LED15") (pin "2-VDD") (pinfunction "VDD_2-VDD") (pintype "power_in"))
      (node (ref "LED16") (pin "2-VDD") (pinfunction "VDD_2-VDD") (pintype "power_in"))
      (node (ref "LED17") (pin "2-VDD") (pinfunction "VDD_2-VDD") (pintype "power_in"))
      (node (ref "LED18") (pin "2-VDD") (pinfunction "VDD_2-VDD") (pintype "power_in"))
      (node (ref "LED19") (pin "2-VDD") (pinfunction "VDD_2-VDD") (pintype "power_in"))
      (node (ref "LED2") (pin "2-VDD") (pinfunction "VDD_2-VDD") (pintype "power_in"))
      (node (ref "LED20") (pin "2-VDD") (pinfunction "VDD_2-VDD") (pintype "power_in"))
      (node (ref "LED21") (pin "2-VDD") (pinfunction "VDD_2-VDD") (pintype "power_in"))
      (node (ref "LED22") (pin "2-VDD") (pinfunction "VDD_2-VDD") (pintype "power_in"))
      (node (ref "LED23") (pin "2-VDD") (pinfunction "VDD_2-VDD") (pintype "power_in"))
      (node (ref "LED24") (pin "2-VDD") (pinfunction "VDD_2-VDD") (pintype "power_in"))
      (node (ref "LED25") (pin "2-VDD") (pinfunction "VDD_2-VDD") (pintype "power_in"))
      (node (ref "LED26") (pin "2-VDD") (pinfunction "VDD_2-VDD") (pintype "power_in"))
      (node (ref "LED27") (pin "2-VDD") (pinfunction "VDD_2-VDD") (pintype "power_in"))
      (node (ref "LED28") (pin "2-VDD") (pinfunction "VDD_2-VDD") (pintype "power_in"))
      (node (ref "LED29") (pin "2-VDD") (pinfunction "VDD_2-VDD") (pintype "power_in"))
      (node (ref "LED3") (pin "2-VDD") (pinfunction "VDD_2-VDD") (pintype "power_in"))
      (node (ref "LED30") (pin "2-VDD") (pinfunction "VDD_2-VDD") (pintype "power_in"))
      (node (ref "LED31") (pin "2-VDD") (pinfunction "VDD_2-VDD") (pintype "power_in"))
      (node (ref "LED32") (pin "2-VDD") (pinfunction "VDD_2-VDD") (pintype "power_in"))
      (node (ref "LED33") (pin "2-VDD") (pinfunction "VDD_2-VDD") (pintype "power_in"))
      (node (ref "LED34") (pin "2-VDD") (pinfunction "VDD_2-VDD") (pintype "power_in"))
      (node (ref "LED35") (pin "2-VDD") (pinfunction "VDD_2-VDD") (pintype "power_in"))
      (node (ref "LED36") (pin "2-VDD") (pinfunction "VDD_2-VDD") (pintype "power_in"))
      (node (ref "LED37") (pin "2-VDD") (pinfunction "VDD_2-VDD") (pintype "power_in"))
      (node (ref "LED38") (pin "2-VDD") (pinfunction "VDD_2-VDD") (pintype "power_in"))
      (node (ref "LED39") (pin "2-VDD") (pinfunction "VDD_2-VDD") (pintype "power_in"))
      (node (ref "LED4") (pin "2-VDD") (pinfunction "VDD_2-VDD") (pintype "power_in"))
      (node (ref "LED40") (pin "2-VDD") (pinfunction "VDD_2-VDD") (pintype "power_in"))
      (node (ref "LED41") (pin "2-VDD") (pinfunction "VDD_2-VDD") (pintype "power_in"))
      (node (ref "LED42") (pin "2-VDD") (pinfunction "VDD_2-VDD") (pintype "power_in"))
      (node (ref "LED43") (pin "2-VDD") (pinfunction "VDD_2-VDD") (pintype "power_in"))
      (node (ref "LED44") (pin "2-VDD") (pinfunction "VDD_2-VDD") (pintype "power_in"))
      (node (ref "LED45") (pin "2-VDD") (pinfunction "VDD_2-VDD") (pintype "power_in"))
      (node (ref "LED46") (pin "2-VDD") (pinfunction "VDD_2-VDD") (pintype "power_in"))
      (node (ref "LED47") (pin "2-VDD") (pinfunction "VDD_2-VDD") (pintype "power_in"))
      (node (ref "LED48") (pin "2-VDD") (pinfunction "VDD_2-VDD") (pintype "power_in"))
      (node (ref "LED49") (pin "2-VDD") (pinfunction "VDD_2-VDD") (pintype "power_in"))
      (node (ref "LED5") (pin "2-VDD") (pinfunction "VDD_2-VDD") (pintype "power_in"))
      (node (ref "LED50") (pin "2-VDD") (pinfunction "VDD_2-VDD") (pintype "power_in"))
      (node (ref "LED51") (pin "2-VDD") (pinfunction "VDD_2-VDD") (pintype "power_in"))
      (node (ref "LED52") (pin "2-VDD") (pinfunction "VDD_2-VDD") (pintype "power_in"))
      (node (ref "LED53") (pin "2-VDD") (pinfunction "VDD_2-VDD") (pintype "power_in"))
      (node (ref "LED54") (pin "2-VDD") (pinfunction "VDD_2-VDD") (pintype "power_in"))
      (node (ref "LED55") (pin "2-VDD") (pinfunction "VDD_2-VDD") (pintype "power_in"))
      (node (ref "LED56") (pin "2-VDD") (pinfunction "VDD_2-VDD") (pintype "power_in"))
      (node (ref "LED57") (pin "2-VDD") (pinfunction "VDD_2-VDD") (pintype "power_in"))
      (node (ref "LED58") (pin "2-VDD") (pinfunction "VDD_2-VDD") (pintype "power_in"))
      (node (ref "LED59") (pin "2-VDD") (pinfunction "VDD_2-VDD") (pintype "power_in"))
      (node (ref "LED6") (pin "2-VDD") (pinfunction "VDD_2-VDD") (pintype "power_in"))
      (node (ref "LED60") (pin "2-VDD") (pinfunction "VDD_2-VDD") (pintype "power_in"))
      (node (ref "LED61") (pin "2-VDD") (pinfunction "VDD_2-VDD") (pintype "power_in"))
      (node (ref "LED62") (pin "2-VDD") (pinfunction "VDD_2-VDD") (pintype "power_in"))
      (node (ref "LED63") (pin "2-VDD") (pinfunction "VDD_2-VDD") (pintype "power_in"))
      (node (ref "LED64") (pin "2-VDD") (pinfunction "VDD_2-VDD") (pintype "power_in"))
      (node (ref "LED65") (pin "2-VDD") (pinfunction "VDD_2-VDD") (pintype "power_in"))
      (node (ref "LED66") (pin "2-VDD") (pinfunction "VDD_2-VDD") (pintype "power_in"))
      (node (ref "LED67") (pin "2-VDD") (pinfunction "VDD_2-VDD") (pintype "power_in"))
      (node (ref "LED68") (pin "2-VDD") (pinfunction "VDD_2-VDD") (pintype "power_in"))
      (node (ref "LED69") (pin "2-VDD") (pinfunction "VDD_2-VDD") (pintype "power_in"))
      (node (ref "LED7") (pin "2-VDD") (pinfunction "VDD_2-VDD") (pintype "power_in"))
      (node (ref "LED70") (pin "2-VDD") (pinfunction "VDD_2-VDD") (pintype "power_in"))
      (node (ref "LED71") (pin "2-VDD") (pinfunction "VDD_2-VDD") (pintype "power_in"))
      (node (ref "LED72") (pin "2-VDD") (pinfunction "VDD_2-VDD") (pintype "power_in"))
      (node (ref "LED73") (pin "2-VDD") (pinfunction "VDD_2-VDD") (pintype "power_in"))
      (node (ref "LED74") (pin "2-VDD") (pinfunction "VDD_2-VDD") (pintype "power_in"))
      (node (ref "LED75") (pin "2-VDD") (pinfunction "VDD_2-VDD") (pintype "power_in"))
      (node (ref "LED76") (pin "2-VDD") (pinfunction "VDD_2-VDD") (pintype "power_in"))
      (node (ref "LED77") (pin "2-VDD") (pinfunction "VDD_2-VDD") (pintype "power_in"))
      (node (ref "LED78") (pin "2-VDD") (pinfunction "VDD_2-VDD") (pintype "power_in"))
      (node (ref "LED79") (pin "2-VDD") (pinfunction "VDD_2-VDD") (pintype "power_in"))
      (node (ref "LED8") (pin "2-VDD") (pinfunction "VDD_2-VDD") (pintype "power_in"))
      (node (ref "LED80") (pin "2-VDD") (pinfunction "VDD_2-VDD") (pintype "power_in"))
      (node (ref "LED81") (pin "2-VDD") (pinfunction "VDD_2-VDD") (pintype "power_in"))
      (node (ref "LED82") (pin "2-VDD") (pinfunction "VDD_2-VDD") (pintype "power_in"))
      (node (ref "LED83") (pin "2-VDD") (pinfunction "VDD_2-VDD") (pintype "power_in"))
      (node (ref "LED84") (pin "2-VDD") (pinfunction "VDD_2-VDD") (pintype "power_in"))
      (node (ref "LED85") (pin "2-VDD") (pinfunction "VDD_2-VDD") (pintype "power_in"))
      (node (ref "LED86") (pin "2-VDD") (pinfunction "VDD_2-VDD") (pintype "power_in"))
      (node (ref "LED87") (pin "2-VDD") (pinfunction "VDD_2-VDD") (pintype "power_in"))
      (node (ref "LED88") (pin "2-VDD") (pinfunction "VDD_2-VDD") (pintype "power_in"))
      (node (ref "LED89") (pin "2-VDD") (pinfunction "VDD_2-VDD") (pintype "power_in"))
      (node (ref "LED9") (pin "2-VDD") (pinfunction "VDD_2-VDD") (pintype "power_in"))
      (node (ref "LED90") (pin "2-VDD") (pinfunction "VDD_2-VDD") (pintype "power_in"))
      (node (ref "LED91") (pin "2-VDD") (pinfunction "VDD_2-VDD") (pintype "power_in"))
      (node (ref "LED92") (pin "2-VDD") (pinfunction "VDD_2-VDD") (pintype "power_in"))
      (node (ref "LED93") (pin "2-VDD") (pinfunction "VDD_2-VDD") (pintype "power_in"))
      (node (ref "LED94") (pin "2-VDD") (pinfunction "VDD_2-VDD") (pintype "power_in"))
      (node (ref "LED95") (pin "2-VDD") (pinfunction "VDD_2-VDD") (pintype "power_in"))
      (node (ref "LED96") (pin "2-VDD") (pinfunction "VDD_2-VDD") (pintype "power_in"))
      (node (ref "LED97") (pin "2-VDD") (pinfunction "VDD_2-VDD") (pintype "power_in"))
      (node (ref "LED98") (pin "2-VDD") (pinfunction "VDD_2-VDD") (pintype "power_in"))
      (node (ref "LED99") (pin "2-VDD") (pinfunction "VDD_2-VDD") (pintype "power_in"))
      (node (ref "R6") (pin "2") (pinfunction "2_2") (pintype "passive"))
      (node (ref "ST1") (pin "1") (pinfunction "1_1") (pintype "bidirectional"))
      (node (ref "U$1") (pin "6") (pinfunction "VCCB_6") (pintype "power_in"))
    )
    (net (code "123") (name "VDDFF1") (class "Default")
      (node (ref "C4") (pin "P$1") (pinfunction "1_P$1") (pintype "passive"))
      (node (ref "F1") (pin "1") (pinfunction "1_1") (pintype "passive"))
      (node (ref "L1") (pin "P$1") (pinfunction "1_P$1") (pintype "passive"))
    )
    (net (code "124") (name "VDDFF2") (class "Default")
      (node (ref "C3") (pin "P$1") (pinfunction "1_P$1") (pintype "passive"))
      (node (ref "F2") (pin "1") (pinfunction "1_1") (pintype "passive"))
      (node (ref "L2") (pin "P$1") (pinfunction "1_P$1") (pintype "passive"))
    )
    (net (code "125") (name "unconnected-(CON1-D+1-PadA6)") (class "Default")
      (node (ref "CON1") (pin "A6") (pinfunction "D+1_A6") (pintype "passive"))
    )
    (net (code "126") (name "unconnected-(CON1-D+2-PadB6)") (class "Default")
      (node (ref "CON1") (pin "B6") (pinfunction "D+2_B6") (pintype "passive"))
    )
    (net (code "127") (name "unconnected-(CON1-D-1-PadA7)") (class "Default")
      (node (ref "CON1") (pin "A7") (pinfunction "D-1_A7") (pintype "passive"))
    )
    (net (code "128") (name "unconnected-(CON1-D-2-PadB7)") (class "Default")
      (node (ref "CON1") (pin "B7") (pinfunction "D-2_B7") (pintype "passive"))
    )
    (net (code "129") (name "unconnected-(CON1-SBU1-PadA8)") (class "Default")
      (node (ref "CON1") (pin "A8") (pinfunction "SBU1_A8") (pintype "passive"))
    )
    (net (code "130") (name "unconnected-(CON1-SBU2-PadB8)") (class "Default")
      (node (ref "CON1") (pin "B8") (pinfunction "SBU2_B8") (pintype "passive"))
    )
    (net (code "131") (name "unconnected-(MS1-AREF-Pad3)") (class "Default")
      (node (ref "MS1") (pin "3") (pinfunction "AREF_3") (pintype "passive"))
    )
    (net (code "132") (name "unconnected-(MS1-EN-Pad27)") (class "Default")
      (node (ref "MS1") (pin "27") (pinfunction "EN_27") (pintype "passive"))
    )
    (net (code "133") (name "unconnected-(MS1-GPIO9-Pad21)") (class "Default")
      (node (ref "MS1") (pin "21") (pinfunction "GPIO9_21") (pintype "bidirectional"))
    )
    (net (code "134") (name "unconnected-(MS1-GPIO10-Pad22)") (class "Default")
      (node (ref "MS1") (pin "22") (pinfunction "GPIO10_22") (pintype "bidirectional"))
    )
    (net (code "135") (name "unconnected-(MS1-GPIO11-Pad23)") (class "Default")
      (node (ref "MS1") (pin "23") (pinfunction "GPIO11_23") (pintype "bidirectional"))
    )
    (net (code "136") (name "unconnected-(MS1-GPIO13-Pad25)") (class "Default")
      (node (ref "MS1") (pin "25") (pinfunction "GPIO13_25") (pintype "bidirectional"))
    )
    (net (code "137") (name "unconnected-(MS1-GPIOA0-Pad5)") (class "Default")
      (node (ref "MS1") (pin "5") (pinfunction "GPIOA0_5") (pintype "bidirectional"))
    )
    (net (code "138") (name "unconnected-(MS1-GPIOA1-Pad6)") (class "Default")
      (node (ref "MS1") (pin "6") (pinfunction "GPIOA1_6") (pintype "bidirectional"))
    )
    (net (code "139") (name "unconnected-(MS1-GPIOA2-Pad7)") (class "Default")
      (node (ref "MS1") (pin "7") (pinfunction "GPIOA2_7") (pintype "bidirectional"))
    )
    (net (code "140") (name "unconnected-(MS1-GPIOA3-Pad8)") (class "Default")
      (node (ref "MS1") (pin "8") (pinfunction "GPIOA3_8") (pintype "bidirectional"))
    )
    (net (code "141") (name "unconnected-(MS1-GPIOA4-Pad9)") (class "Default")
      (node (ref "MS1") (pin "9") (pinfunction "GPIOA4_9") (pintype "bidirectional"))
    )
    (net (code "142") (name "unconnected-(MS1-GPIOA5-Pad10)") (class "Default")
      (node (ref "MS1") (pin "10") (pinfunction "GPIOA5_10") (pintype "bidirectional"))
    )
    (net (code "143") (name "unconnected-(MS1-GPIOMISO-Pad13)") (class "Default")
      (node (ref "MS1") (pin "13") (pinfunction "GPIOMISO_13") (pintype "bidirectional"))
    )
    (net (code "144") (name "unconnected-(MS1-GPIORX-Pad14)") (class "Default")
      (node (ref "MS1") (pin "14") (pinfunction "GPIORX_14") (pintype "bidirectional"))
    )
    (net (code "145") (name "unconnected-(MS1-GPIOSCK-Pad11)") (class "Default")
      (node (ref "MS1") (pin "11") (pinfunction "GPIOSCK_11") (pintype "bidirectional"))
    )
    (net (code "146") (name "unconnected-(MS1-GPIOSCL-Pad18)") (class "Default")
      (node (ref "MS1") (pin "18") (pinfunction "GPIOSCL_18") (pintype "bidirectional"))
    )
    (net (code "147") (name "unconnected-(MS1-GPIOSDA-Pad17)") (class "Default")
      (node (ref "MS1") (pin "17") (pinfunction "GPIOSDA_17") (pintype "bidirectional"))
    )
    (net (code "148") (name "unconnected-(MS1-GPIOTX-Pad15)") (class "Default")
      (node (ref "MS1") (pin "15") (pinfunction "GPIOTX_15") (pintype "bidirectional"))
    )
    (net (code "149") (name "unconnected-(MS1-NC-Pad16)") (class "Default")
      (node (ref "MS1") (pin "16") (pinfunction "NC_16") (pintype "passive"))
    )
    (net (code "150") (name "{slash}RESET") (class "Default")
      (node (ref "MS1") (pin "1") (pinfunction "~{RESET}_1") (pintype "input"))
      (node (ref "S1") (pin "1") (pinfunction "1_1") (pintype "passive"))
      (node (ref "S1") (pin "2") (pinfunction "2_2") (pintype "passive"))
      (node (ref "S1") (pin "7") (pinfunction "1_7") (pintype "passive"))
      (node (ref "S1") (pin "8") (pinfunction "2_8") (pintype "passive"))
    )
  )
)
